# LED-zero-SHIM.net
KiCad netlist of a schematic drawn in EAGLE
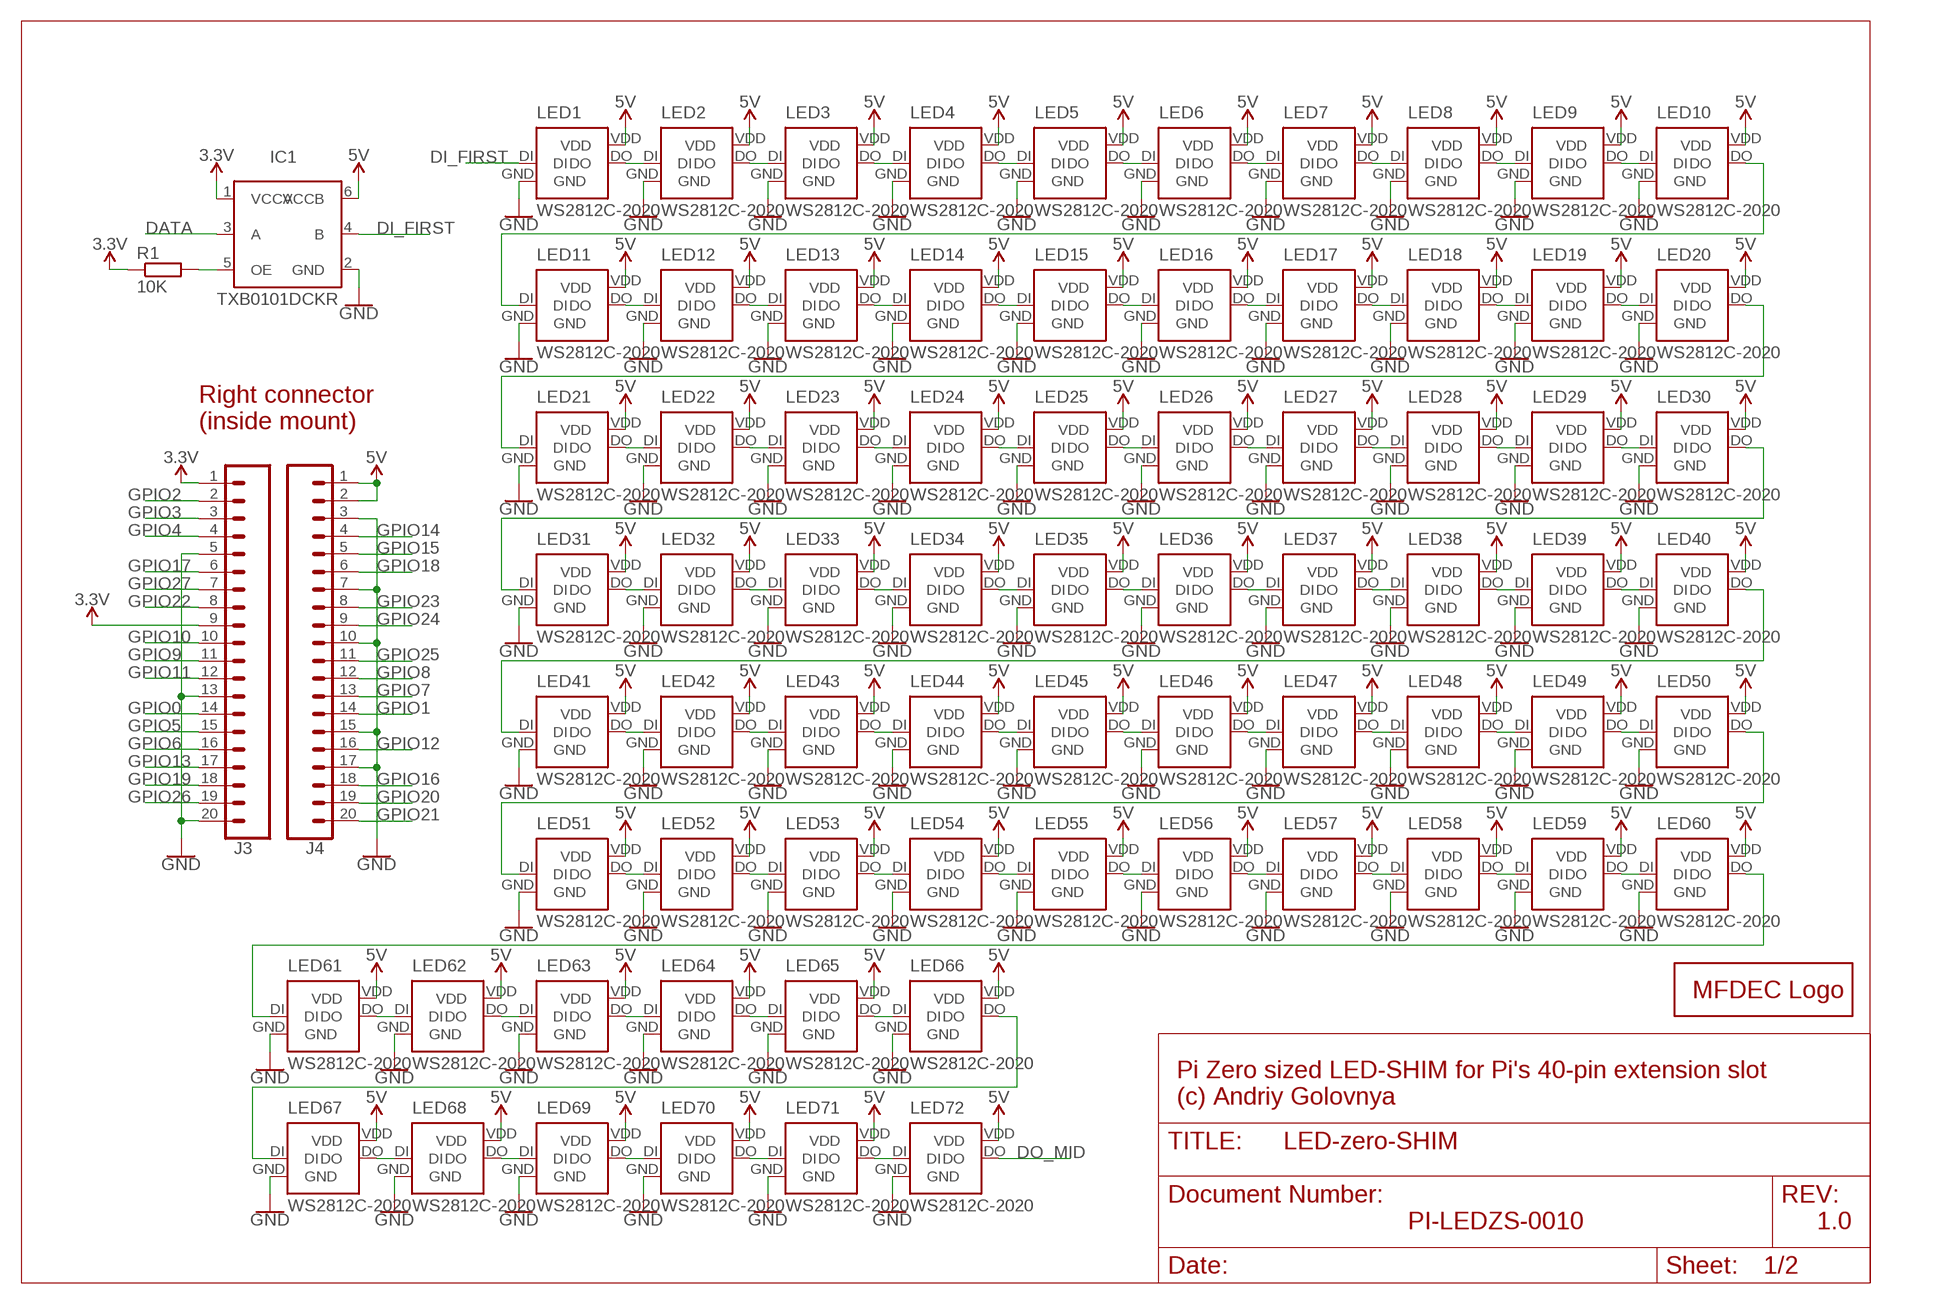
[diagram p0: schematic, sheet 1]
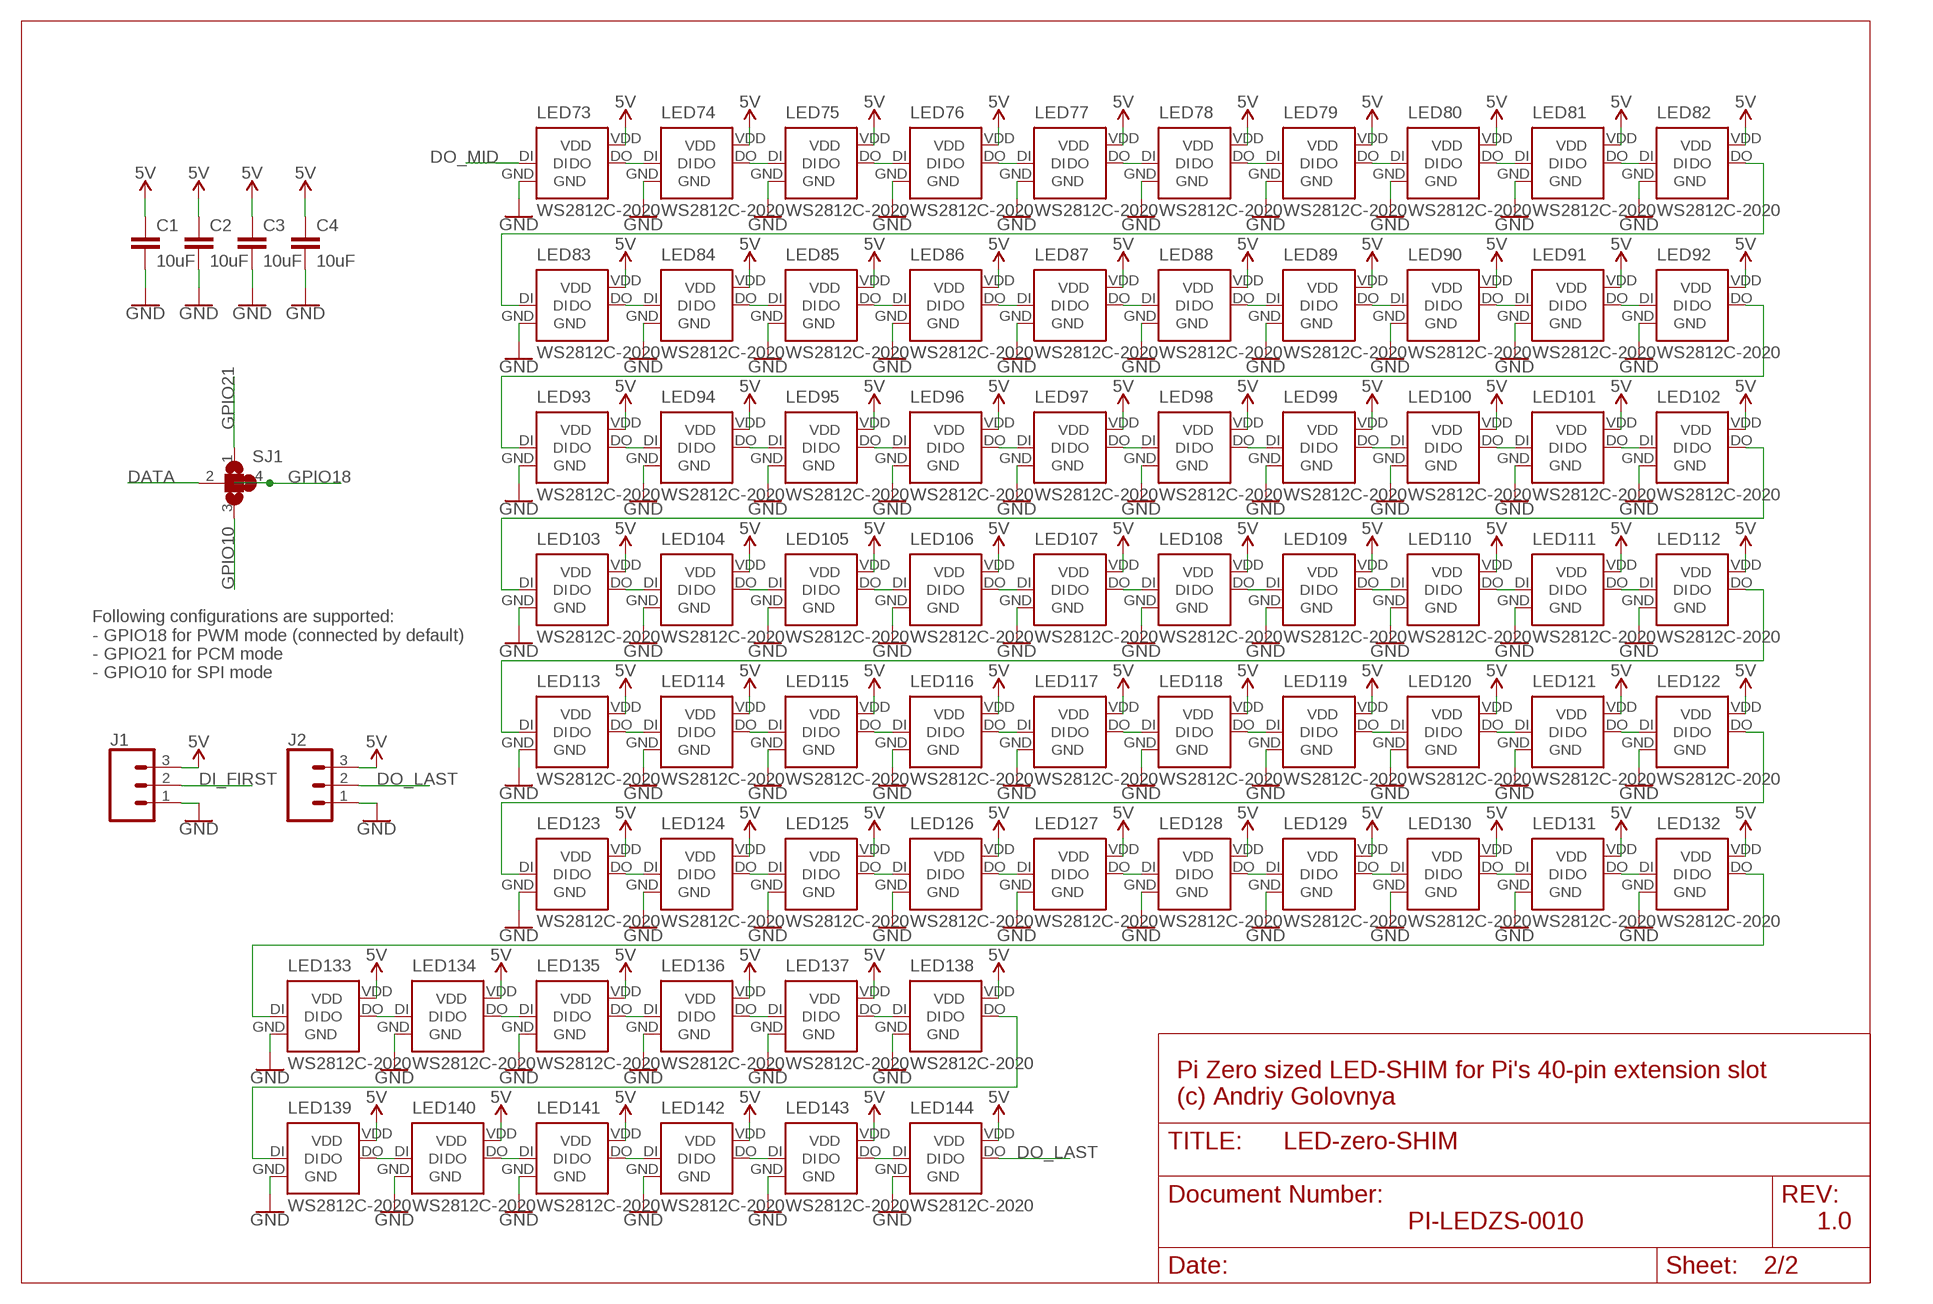
[diagram p1: schematic, sheet 2]

(export (version "E")
  (design (tool "Eeschema 10.0.6"))
  (components
    (comp (ref "IC1")
      (value "TXB0101DCKR")
      (footprint "eagle-import:SOT65P210X110-6N")
      (libsource (lib "eagle-import") (part "TXB0101DCKR"))
    )
    (comp (ref "J3")
      (value "CONN_20LOCK")
      (footprint "eagle-import:1X20_LOCK")
      (libsource (lib "eagle-import") (part "CONN_20LOCK"))
    )
    (comp (ref "J4")
      (value "CONN_20LOCK")
      (footprint "eagle-import:1X20_LOCK")
      (libsource (lib "eagle-import") (part "CONN_20LOCK"))
    )
    (comp (ref "LED1")
      (value "WS2812C-2020")
      (footprint "eagle-import:WS2812X-2020")
      (libsource (lib "eagle-import") (part "WS2812C-2020"))
    )
    (comp (ref "LED2")
      (value "WS2812C-2020")
      (footprint "eagle-import:WS2812X-2020")
      (libsource (lib "eagle-import") (part "WS2812C-2020"))
    )
    (comp (ref "LED3")
      (value "WS2812C-2020")
      (footprint "eagle-import:WS2812X-2020")
      (libsource (lib "eagle-import") (part "WS2812C-2020"))
    )
    (comp (ref "LED4")
      (value "WS2812C-2020")
      (footprint "eagle-import:WS2812X-2020")
      (libsource (lib "eagle-import") (part "WS2812C-2020"))
    )
    (comp (ref "LED5")
      (value "WS2812C-2020")
      (footprint "eagle-import:WS2812X-2020")
      (libsource (lib "eagle-import") (part "WS2812C-2020"))
    )
    (comp (ref "LED6")
      (value "WS2812C-2020")
      (footprint "eagle-import:WS2812X-2020")
      (libsource (lib "eagle-import") (part "WS2812C-2020"))
    )
    (comp (ref "LED7")
      (value "WS2812C-2020")
      (footprint "eagle-import:WS2812X-2020")
      (libsource (lib "eagle-import") (part "WS2812C-2020"))
    )
    (comp (ref "LED8")
      (value "WS2812C-2020")
      (footprint "eagle-import:WS2812X-2020")
      (libsource (lib "eagle-import") (part "WS2812C-2020"))
    )
    (comp (ref "LED9")
      (value "WS2812C-2020")
      (footprint "eagle-import:WS2812X-2020")
      (libsource (lib "eagle-import") (part "WS2812C-2020"))
    )
    (comp (ref "LED10")
      (value "WS2812C-2020")
      (footprint "eagle-import:WS2812X-2020")
      (libsource (lib "eagle-import") (part "WS2812C-2020"))
    )
    (comp (ref "LED11")
      (value "WS2812C-2020")
      (footprint "eagle-import:WS2812X-2020")
      (libsource (lib "eagle-import") (part "WS2812C-2020"))
    )
    (comp (ref "LED12")
      (value "WS2812C-2020")
      (footprint "eagle-import:WS2812X-2020")
      (libsource (lib "eagle-import") (part "WS2812C-2020"))
    )
    (comp (ref "LED13")
      (value "WS2812C-2020")
      (footprint "eagle-import:WS2812X-2020")
      (libsource (lib "eagle-import") (part "WS2812C-2020"))
    )
    (comp (ref "LED14")
      (value "WS2812C-2020")
      (footprint "eagle-import:WS2812X-2020")
      (libsource (lib "eagle-import") (part "WS2812C-2020"))
    )
    (comp (ref "LED15")
      (value "WS2812C-2020")
      (footprint "eagle-import:WS2812X-2020")
      (libsource (lib "eagle-import") (part "WS2812C-2020"))
    )
    (comp (ref "LED16")
      (value "WS2812C-2020")
      (footprint "eagle-import:WS2812X-2020")
      (libsource (lib "eagle-import") (part "WS2812C-2020"))
    )
    (comp (ref "LED17")
      (value "WS2812C-2020")
      (footprint "eagle-import:WS2812X-2020")
      (libsource (lib "eagle-import") (part "WS2812C-2020"))
    )
    (comp (ref "LED18")
      (value "WS2812C-2020")
      (footprint "eagle-import:WS2812X-2020")
      (libsource (lib "eagle-import") (part "WS2812C-2020"))
    )
    (comp (ref "LED19")
      (value "WS2812C-2020")
      (footprint "eagle-import:WS2812X-2020")
      (libsource (lib "eagle-import") (part "WS2812C-2020"))
    )
    (comp (ref "LED20")
      (value "WS2812C-2020")
      (footprint "eagle-import:WS2812X-2020")
      (libsource (lib "eagle-import") (part "WS2812C-2020"))
    )
    (comp (ref "LED21")
      (value "WS2812C-2020")
      (footprint "eagle-import:WS2812X-2020")
      (libsource (lib "eagle-import") (part "WS2812C-2020"))
    )
    (comp (ref "LED22")
      (value "WS2812C-2020")
      (footprint "eagle-import:WS2812X-2020")
      (libsource (lib "eagle-import") (part "WS2812C-2020"))
    )
    (comp (ref "LED23")
      (value "WS2812C-2020")
      (footprint "eagle-import:WS2812X-2020")
      (libsource (lib "eagle-import") (part "WS2812C-2020"))
    )
    (comp (ref "LED24")
      (value "WS2812C-2020")
      (footprint "eagle-import:WS2812X-2020")
      (libsource (lib "eagle-import") (part "WS2812C-2020"))
    )
    (comp (ref "LED25")
      (value "WS2812C-2020")
      (footprint "eagle-import:WS2812X-2020")
      (libsource (lib "eagle-import") (part "WS2812C-2020"))
    )
    (comp (ref "LED26")
      (value "WS2812C-2020")
      (footprint "eagle-import:WS2812X-2020")
      (libsource (lib "eagle-import") (part "WS2812C-2020"))
    )
    (comp (ref "LED27")
      (value "WS2812C-2020")
      (footprint "eagle-import:WS2812X-2020")
      (libsource (lib "eagle-import") (part "WS2812C-2020"))
    )
    (comp (ref "LED28")
      (value "WS2812C-2020")
      (footprint "eagle-import:WS2812X-2020")
      (libsource (lib "eagle-import") (part "WS2812C-2020"))
    )
    (comp (ref "LED29")
      (value "WS2812C-2020")
      (footprint "eagle-import:WS2812X-2020")
      (libsource (lib "eagle-import") (part "WS2812C-2020"))
    )
    (comp (ref "LED30")
      (value "WS2812C-2020")
      (footprint "eagle-import:WS2812X-2020")
      (libsource (lib "eagle-import") (part "WS2812C-2020"))
    )
    (comp (ref "LED31")
      (value "WS2812C-2020")
      (footprint "eagle-import:WS2812X-2020")
      (libsource (lib "eagle-import") (part "WS2812C-2020"))
    )
    (comp (ref "LED32")
      (value "WS2812C-2020")
      (footprint "eagle-import:WS2812X-2020")
      (libsource (lib "eagle-import") (part "WS2812C-2020"))
    )
    (comp (ref "LED33")
      (value "WS2812C-2020")
      (footprint "eagle-import:WS2812X-2020")
      (libsource (lib "eagle-import") (part "WS2812C-2020"))
    )
    (comp (ref "LED34")
      (value "WS2812C-2020")
      (footprint "eagle-import:WS2812X-2020")
      (libsource (lib "eagle-import") (part "WS2812C-2020"))
    )
    (comp (ref "LED35")
      (value "WS2812C-2020")
      (footprint "eagle-import:WS2812X-2020")
      (libsource (lib "eagle-import") (part "WS2812C-2020"))
    )
    (comp (ref "LED36")
      (value "WS2812C-2020")
      (footprint "eagle-import:WS2812X-2020")
      (libsource (lib "eagle-import") (part "WS2812C-2020"))
    )
    (comp (ref "LED37")
      (value "WS2812C-2020")
      (footprint "eagle-import:WS2812X-2020")
      (libsource (lib "eagle-import") (part "WS2812C-2020"))
    )
    (comp (ref "LED38")
      (value "WS2812C-2020")
      (footprint "eagle-import:WS2812X-2020")
      (libsource (lib "eagle-import") (part "WS2812C-2020"))
    )
    (comp (ref "LED39")
      (value "WS2812C-2020")
      (footprint "eagle-import:WS2812X-2020")
      (libsource (lib "eagle-import") (part "WS2812C-2020"))
    )
    (comp (ref "LED40")
      (value "WS2812C-2020")
      (footprint "eagle-import:WS2812X-2020")
      (libsource (lib "eagle-import") (part "WS2812C-2020"))
    )
    (comp (ref "LED41")
      (value "WS2812C-2020")
      (footprint "eagle-import:WS2812X-2020")
      (libsource (lib "eagle-import") (part "WS2812C-2020"))
    )
    (comp (ref "LED42")
      (value "WS2812C-2020")
      (footprint "eagle-import:WS2812X-2020")
      (libsource (lib "eagle-import") (part "WS2812C-2020"))
    )
    (comp (ref "LED43")
      (value "WS2812C-2020")
      (footprint "eagle-import:WS2812X-2020")
      (libsource (lib "eagle-import") (part "WS2812C-2020"))
    )
    (comp (ref "LED44")
      (value "WS2812C-2020")
      (footprint "eagle-import:WS2812X-2020")
      (libsource (lib "eagle-import") (part "WS2812C-2020"))
    )
    (comp (ref "LED45")
      (value "WS2812C-2020")
      (footprint "eagle-import:WS2812X-2020")
      (libsource (lib "eagle-import") (part "WS2812C-2020"))
    )
    (comp (ref "LED46")
      (value "WS2812C-2020")
      (footprint "eagle-import:WS2812X-2020")
      (libsource (lib "eagle-import") (part "WS2812C-2020"))
    )
    (comp (ref "LED47")
      (value "WS2812C-2020")
      (footprint "eagle-import:WS2812X-2020")
      (libsource (lib "eagle-import") (part "WS2812C-2020"))
    )
    (comp (ref "LED48")
      (value "WS2812C-2020")
      (footprint "eagle-import:WS2812X-2020")
      (libsource (lib "eagle-import") (part "WS2812C-2020"))
    )
    (comp (ref "LED49")
      (value "WS2812C-2020")
      (footprint "eagle-import:WS2812X-2020")
      (libsource (lib "eagle-import") (part "WS2812C-2020"))
    )
    (comp (ref "LED50")
      (value "WS2812C-2020")
      (footprint "eagle-import:WS2812X-2020")
      (libsource (lib "eagle-import") (part "WS2812C-2020"))
    )
    (comp (ref "LED51")
      (value "WS2812C-2020")
      (footprint "eagle-import:WS2812X-2020")
      (libsource (lib "eagle-import") (part "WS2812C-2020"))
    )
    (comp (ref "LED52")
      (value "WS2812C-2020")
      (footprint "eagle-import:WS2812X-2020")
      (libsource (lib "eagle-import") (part "WS2812C-2020"))
    )
    (comp (ref "LED53")
      (value "WS2812C-2020")
      (footprint "eagle-import:WS2812X-2020")
      (libsource (lib "eagle-import") (part "WS2812C-2020"))
    )
    (comp (ref "LED54")
      (value "WS2812C-2020")
      (footprint "eagle-import:WS2812X-2020")
      (libsource (lib "eagle-import") (part "WS2812C-2020"))
    )
    (comp (ref "LED55")
      (value "WS2812C-2020")
      (footprint "eagle-import:WS2812X-2020")
      (libsource (lib "eagle-import") (part "WS2812C-2020"))
    )
    (comp (ref "LED56")
      (value "WS2812C-2020")
      (footprint "eagle-import:WS2812X-2020")
      (libsource (lib "eagle-import") (part "WS2812C-2020"))
    )
    (comp (ref "LED57")
      (value "WS2812C-2020")
      (footprint "eagle-import:WS2812X-2020")
      (libsource (lib "eagle-import") (part "WS2812C-2020"))
    )
    (comp (ref "LED58")
      (value "WS2812C-2020")
      (footprint "eagle-import:WS2812X-2020")
      (libsource (lib "eagle-import") (part "WS2812C-2020"))
    )
    (comp (ref "LED59")
      (value "WS2812C-2020")
      (footprint "eagle-import:WS2812X-2020")
      (libsource (lib "eagle-import") (part "WS2812C-2020"))
    )
    (comp (ref "LED60")
      (value "WS2812C-2020")
      (footprint "eagle-import:WS2812X-2020")
      (libsource (lib "eagle-import") (part "WS2812C-2020"))
    )
    (comp (ref "LED61")
      (value "WS2812C-2020")
      (footprint "eagle-import:WS2812X-2020")
      (libsource (lib "eagle-import") (part "WS2812C-2020"))
    )
    (comp (ref "LED62")
      (value "WS2812C-2020")
      (footprint "eagle-import:WS2812X-2020")
      (libsource (lib "eagle-import") (part "WS2812C-2020"))
    )
    (comp (ref "LED63")
      (value "WS2812C-2020")
      (footprint "eagle-import:WS2812X-2020")
      (libsource (lib "eagle-import") (part "WS2812C-2020"))
    )
    (comp (ref "LED64")
      (value "WS2812C-2020")
      (footprint "eagle-import:WS2812X-2020")
      (libsource (lib "eagle-import") (part "WS2812C-2020"))
    )
    (comp (ref "LED65")
      (value "WS2812C-2020")
      (footprint "eagle-import:WS2812X-2020")
      (libsource (lib "eagle-import") (part "WS2812C-2020"))
    )
    (comp (ref "LED66")
      (value "WS2812C-2020")
      (footprint "eagle-import:WS2812X-2020")
      (libsource (lib "eagle-import") (part "WS2812C-2020"))
    )
    (comp (ref "LED67")
      (value "WS2812C-2020")
      (footprint "eagle-import:WS2812X-2020")
      (libsource (lib "eagle-import") (part "WS2812C-2020"))
    )
    (comp (ref "LED68")
      (value "WS2812C-2020")
      (footprint "eagle-import:WS2812X-2020")
      (libsource (lib "eagle-import") (part "WS2812C-2020"))
    )
    (comp (ref "LED69")
      (value "WS2812C-2020")
      (footprint "eagle-import:WS2812X-2020")
      (libsource (lib "eagle-import") (part "WS2812C-2020"))
    )
    (comp (ref "LED70")
      (value "WS2812C-2020")
      (footprint "eagle-import:WS2812X-2020")
      (libsource (lib "eagle-import") (part "WS2812C-2020"))
    )
    (comp (ref "LED71")
      (value "WS2812C-2020")
      (footprint "eagle-import:WS2812X-2020")
      (libsource (lib "eagle-import") (part "WS2812C-2020"))
    )
    (comp (ref "LED72")
      (value "WS2812C-2020")
      (footprint "eagle-import:WS2812X-2020")
      (libsource (lib "eagle-import") (part "WS2812C-2020"))
    )
    (comp (ref "LOGO1")
      (value "MFDECLOGO_L_30MM")
      (footprint "eagle-import:MFDEC_L_30MM")
      (libsource (lib "eagle-import") (part "MFDECLOGO_L_30MM"))
    )
    (comp (ref "R1")
      (value "10K")
      (footprint "eagle-import:R0402")
      (libsource (lib "eagle-import") (part "R-EU_R0402"))
    )
    (comp (ref "C1")
      (value "10uF")
      (footprint "eagle-import:C0805")
      (libsource (lib "eagle-import") (part "C-EUC0805"))
    )
    (comp (ref "C2")
      (value "10uF")
      (footprint "eagle-import:C0805")
      (libsource (lib "eagle-import") (part "C-EUC0805"))
    )
    (comp (ref "C3")
      (value "10uF")
      (footprint "eagle-import:C0805")
      (libsource (lib "eagle-import") (part "C-EUC0805"))
    )
    (comp (ref "C4")
      (value "10uF")
      (footprint "eagle-import:C0805")
      (libsource (lib "eagle-import") (part "C-EUC0805"))
    )
    (comp (ref "J1")
      (value "CONN_03")
      (footprint "eagle-import:1X03")
      (libsource (lib "eagle-import") (part "CONN_03"))
    )
    (comp (ref "J2")
      (value "CONN_03")
      (footprint "eagle-import:1X03")
      (libsource (lib "eagle-import") (part "CONN_03"))
    )
    (comp (ref "LED73")
      (value "WS2812C-2020")
      (footprint "eagle-import:WS2812X-2020")
      (libsource (lib "eagle-import") (part "WS2812C-2020"))
    )
    (comp (ref "LED74")
      (value "WS2812C-2020")
      (footprint "eagle-import:WS2812X-2020")
      (libsource (lib "eagle-import") (part "WS2812C-2020"))
    )
    (comp (ref "LED75")
      (value "WS2812C-2020")
      (footprint "eagle-import:WS2812X-2020")
      (libsource (lib "eagle-import") (part "WS2812C-2020"))
    )
    (comp (ref "LED76")
      (value "WS2812C-2020")
      (footprint "eagle-import:WS2812X-2020")
      (libsource (lib "eagle-import") (part "WS2812C-2020"))
    )
    (comp (ref "LED77")
      (value "WS2812C-2020")
      (footprint "eagle-import:WS2812X-2020")
      (libsource (lib "eagle-import") (part "WS2812C-2020"))
    )
    (comp (ref "LED78")
      (value "WS2812C-2020")
      (footprint "eagle-import:WS2812X-2020")
      (libsource (lib "eagle-import") (part "WS2812C-2020"))
    )
    (comp (ref "LED79")
      (value "WS2812C-2020")
      (footprint "eagle-import:WS2812X-2020")
      (libsource (lib "eagle-import") (part "WS2812C-2020"))
    )
    (comp (ref "LED80")
      (value "WS2812C-2020")
      (footprint "eagle-import:WS2812X-2020")
      (libsource (lib "eagle-import") (part "WS2812C-2020"))
    )
    (comp (ref "LED81")
      (value "WS2812C-2020")
      (footprint "eagle-import:WS2812X-2020")
      (libsource (lib "eagle-import") (part "WS2812C-2020"))
    )
    (comp (ref "LED82")
      (value "WS2812C-2020")
      (footprint "eagle-import:WS2812X-2020")
      (libsource (lib "eagle-import") (part "WS2812C-2020"))
    )
    (comp (ref "LED83")
      (value "WS2812C-2020")
      (footprint "eagle-import:WS2812X-2020")
      (libsource (lib "eagle-import") (part "WS2812C-2020"))
    )
    (comp (ref "LED84")
      (value "WS2812C-2020")
      (footprint "eagle-import:WS2812X-2020")
      (libsource (lib "eagle-import") (part "WS2812C-2020"))
    )
    (comp (ref "LED85")
      (value "WS2812C-2020")
      (footprint "eagle-import:WS2812X-2020")
      (libsource (lib "eagle-import") (part "WS2812C-2020"))
    )
    (comp (ref "LED86")
      (value "WS2812C-2020")
      (footprint "eagle-import:WS2812X-2020")
      (libsource (lib "eagle-import") (part "WS2812C-2020"))
    )
    (comp (ref "LED87")
      (value "WS2812C-2020")
      (footprint "eagle-import:WS2812X-2020")
      (libsource (lib "eagle-import") (part "WS2812C-2020"))
    )
    (comp (ref "LED88")
      (value "WS2812C-2020")
      (footprint "eagle-import:WS2812X-2020")
      (libsource (lib "eagle-import") (part "WS2812C-2020"))
    )
    (comp (ref "LED89")
      (value "WS2812C-2020")
      (footprint "eagle-import:WS2812X-2020")
      (libsource (lib "eagle-import") (part "WS2812C-2020"))
    )
    (comp (ref "LED90")
      (value "WS2812C-2020")
      (footprint "eagle-import:WS2812X-2020")
      (libsource (lib "eagle-import") (part "WS2812C-2020"))
    )
    (comp (ref "LED91")
      (value "WS2812C-2020")
      (footprint "eagle-import:WS2812X-2020")
      (libsource (lib "eagle-import") (part "WS2812C-2020"))
    )
    (comp (ref "LED92")
      (value "WS2812C-2020")
      (footprint "eagle-import:WS2812X-2020")
      (libsource (lib "eagle-import") (part "WS2812C-2020"))
    )
    (comp (ref "LED93")
      (value "WS2812C-2020")
      (footprint "eagle-import:WS2812X-2020")
      (libsource (lib "eagle-import") (part "WS2812C-2020"))
    )
    (comp (ref "LED94")
      (value "WS2812C-2020")
      (footprint "eagle-import:WS2812X-2020")
      (libsource (lib "eagle-import") (part "WS2812C-2020"))
    )
    (comp (ref "LED95")
      (value "WS2812C-2020")
      (footprint "eagle-import:WS2812X-2020")
      (libsource (lib "eagle-import") (part "WS2812C-2020"))
    )
    (comp (ref "LED96")
      (value "WS2812C-2020")
      (footprint "eagle-import:WS2812X-2020")
      (libsource (lib "eagle-import") (part "WS2812C-2020"))
    )
    (comp (ref "LED97")
      (value "WS2812C-2020")
      (footprint "eagle-import:WS2812X-2020")
      (libsource (lib "eagle-import") (part "WS2812C-2020"))
    )
    (comp (ref "LED98")
      (value "WS2812C-2020")
      (footprint "eagle-import:WS2812X-2020")
      (libsource (lib "eagle-import") (part "WS2812C-2020"))
    )
    (comp (ref "LED99")
      (value "WS2812C-2020")
      (footprint "eagle-import:WS2812X-2020")
      (libsource (lib "eagle-import") (part "WS2812C-2020"))
    )
    (comp (ref "LED100")
      (value "WS2812C-2020")
      (footprint "eagle-import:WS2812X-2020")
      (libsource (lib "eagle-import") (part "WS2812C-2020"))
    )
    (comp (ref "LED101")
      (value "WS2812C-2020")
      (footprint "eagle-import:WS2812X-2020")
      (libsource (lib "eagle-import") (part "WS2812C-2020"))
    )
    (comp (ref "LED102")
      (value "WS2812C-2020")
      (footprint "eagle-import:WS2812X-2020")
      (libsource (lib "eagle-import") (part "WS2812C-2020"))
    )
    (comp (ref "LED103")
      (value "WS2812C-2020")
      (footprint "eagle-import:WS2812X-2020")
      (libsource (lib "eagle-import") (part "WS2812C-2020"))
    )
    (comp (ref "LED104")
      (value "WS2812C-2020")
      (footprint "eagle-import:WS2812X-2020")
      (libsource (lib "eagle-import") (part "WS2812C-2020"))
    )
    (comp (ref "LED105")
      (value "WS2812C-2020")
      (footprint "eagle-import:WS2812X-2020")
      (libsource (lib "eagle-import") (part "WS2812C-2020"))
    )
    (comp (ref "LED106")
      (value "WS2812C-2020")
      (footprint "eagle-import:WS2812X-2020")
      (libsource (lib "eagle-import") (part "WS2812C-2020"))
    )
    (comp (ref "LED107")
      (value "WS2812C-2020")
      (footprint "eagle-import:WS2812X-2020")
      (libsource (lib "eagle-import") (part "WS2812C-2020"))
    )
    (comp (ref "LED108")
      (value "WS2812C-2020")
      (footprint "eagle-import:WS2812X-2020")
      (libsource (lib "eagle-import") (part "WS2812C-2020"))
    )
    (comp (ref "LED109")
      (value "WS2812C-2020")
      (footprint "eagle-import:WS2812X-2020")
      (libsource (lib "eagle-import") (part "WS2812C-2020"))
    )
    (comp (ref "LED110")
      (value "WS2812C-2020")
      (footprint "eagle-import:WS2812X-2020")
      (libsource (lib "eagle-import") (part "WS2812C-2020"))
    )
    (comp (ref "LED111")
      (value "WS2812C-2020")
      (footprint "eagle-import:WS2812X-2020")
      (libsource (lib "eagle-import") (part "WS2812C-2020"))
    )
    (comp (ref "LED112")
      (value "WS2812C-2020")
      (footprint "eagle-import:WS2812X-2020")
      (libsource (lib "eagle-import") (part "WS2812C-2020"))
    )
    (comp (ref "LED113")
      (value "WS2812C-2020")
      (footprint "eagle-import:WS2812X-2020")
      (libsource (lib "eagle-import") (part "WS2812C-2020"))
    )
    (comp (ref "LED114")
      (value "WS2812C-2020")
      (footprint "eagle-import:WS2812X-2020")
      (libsource (lib "eagle-import") (part "WS2812C-2020"))
    )
    (comp (ref "LED115")
      (value "WS2812C-2020")
      (footprint "eagle-import:WS2812X-2020")
      (libsource (lib "eagle-import") (part "WS2812C-2020"))
    )
    (comp (ref "LED116")
      (value "WS2812C-2020")
      (footprint "eagle-import:WS2812X-2020")
      (libsource (lib "eagle-import") (part "WS2812C-2020"))
    )
    (comp (ref "LED117")
      (value "WS2812C-2020")
      (footprint "eagle-import:WS2812X-2020")
      (libsource (lib "eagle-import") (part "WS2812C-2020"))
    )
    (comp (ref "LED118")
      (value "WS2812C-2020")
      (footprint "eagle-import:WS2812X-2020")
      (libsource (lib "eagle-import") (part "WS2812C-2020"))
    )
    (comp (ref "LED119")
      (value "WS2812C-2020")
      (footprint "eagle-import:WS2812X-2020")
      (libsource (lib "eagle-import") (part "WS2812C-2020"))
    )
    (comp (ref "LED120")
      (value "WS2812C-2020")
      (footprint "eagle-import:WS2812X-2020")
      (libsource (lib "eagle-import") (part "WS2812C-2020"))
    )
    (comp (ref "LED121")
      (value "WS2812C-2020")
      (footprint "eagle-import:WS2812X-2020")
      (libsource (lib "eagle-import") (part "WS2812C-2020"))
    )
    (comp (ref "LED122")
      (value "WS2812C-2020")
      (footprint "eagle-import:WS2812X-2020")
      (libsource (lib "eagle-import") (part "WS2812C-2020"))
    )
    (comp (ref "LED123")
      (value "WS2812C-2020")
      (footprint "eagle-import:WS2812X-2020")
      (libsource (lib "eagle-import") (part "WS2812C-2020"))
    )
    (comp (ref "LED124")
      (value "WS2812C-2020")
      (footprint "eagle-import:WS2812X-2020")
      (libsource (lib "eagle-import") (part "WS2812C-2020"))
    )
    (comp (ref "LED125")
      (value "WS2812C-2020")
      (footprint "eagle-import:WS2812X-2020")
      (libsource (lib "eagle-import") (part "WS2812C-2020"))
    )
    (comp (ref "LED126")
      (value "WS2812C-2020")
      (footprint "eagle-import:WS2812X-2020")
      (libsource (lib "eagle-import") (part "WS2812C-2020"))
    )
    (comp (ref "LED127")
      (value "WS2812C-2020")
      (footprint "eagle-import:WS2812X-2020")
      (libsource (lib "eagle-import") (part "WS2812C-2020"))
    )
    (comp (ref "LED128")
      (value "WS2812C-2020")
      (footprint "eagle-import:WS2812X-2020")
      (libsource (lib "eagle-import") (part "WS2812C-2020"))
    )
    (comp (ref "LED129")
      (value "WS2812C-2020")
      (footprint "eagle-import:WS2812X-2020")
      (libsource (lib "eagle-import") (part "WS2812C-2020"))
    )
    (comp (ref "LED130")
      (value "WS2812C-2020")
      (footprint "eagle-import:WS2812X-2020")
      (libsource (lib "eagle-import") (part "WS2812C-2020"))
    )
    (comp (ref "LED131")
      (value "WS2812C-2020")
      (footprint "eagle-import:WS2812X-2020")
      (libsource (lib "eagle-import") (part "WS2812C-2020"))
    )
    (comp (ref "LED132")
      (value "WS2812C-2020")
      (footprint "eagle-import:WS2812X-2020")
      (libsource (lib "eagle-import") (part "WS2812C-2020"))
    )
    (comp (ref "LED133")
      (value "WS2812C-2020")
      (footprint "eagle-import:WS2812X-2020")
      (libsource (lib "eagle-import") (part "WS2812C-2020"))
    )
    (comp (ref "LED134")
      (value "WS2812C-2020")
      (footprint "eagle-import:WS2812X-2020")
      (libsource (lib "eagle-import") (part "WS2812C-2020"))
    )
    (comp (ref "LED135")
      (value "WS2812C-2020")
      (footprint "eagle-import:WS2812X-2020")
      (libsource (lib "eagle-import") (part "WS2812C-2020"))
    )
    (comp (ref "LED136")
      (value "WS2812C-2020")
      (footprint "eagle-import:WS2812X-2020")
      (libsource (lib "eagle-import") (part "WS2812C-2020"))
    )
    (comp (ref "LED137")
      (value "WS2812C-2020")
      (footprint "eagle-import:WS2812X-2020")
      (libsource (lib "eagle-import") (part "WS2812C-2020"))
    )
    (comp (ref "LED138")
      (value "WS2812C-2020")
      (footprint "eagle-import:WS2812X-2020")
      (libsource (lib "eagle-import") (part "WS2812C-2020"))
    )
    (comp (ref "LED139")
      (value "WS2812C-2020")
      (footprint "eagle-import:WS2812X-2020")
      (libsource (lib "eagle-import") (part "WS2812C-2020"))
    )
    (comp (ref "LED140")
      (value "WS2812C-2020")
      (footprint "eagle-import:WS2812X-2020")
      (libsource (lib "eagle-import") (part "WS2812C-2020"))
    )
    (comp (ref "LED141")
      (value "WS2812C-2020")
      (footprint "eagle-import:WS2812X-2020")
      (libsource (lib "eagle-import") (part "WS2812C-2020"))
    )
    (comp (ref "LED142")
      (value "WS2812C-2020")
      (footprint "eagle-import:WS2812X-2020")
      (libsource (lib "eagle-import") (part "WS2812C-2020"))
    )
    (comp (ref "LED143")
      (value "WS2812C-2020")
      (footprint "eagle-import:WS2812X-2020")
      (libsource (lib "eagle-import") (part "WS2812C-2020"))
    )
    (comp (ref "LED144")
      (value "WS2812C-2020")
      (footprint "eagle-import:WS2812X-2020")
      (libsource (lib "eagle-import") (part "WS2812C-2020"))
    )
    (comp (ref "SJ1")
      (value "SJ3")
      (footprint "eagle-import:SJ_3")
      (libsource (lib "eagle-import") (part "SJ3"))
    )
  )
  (nets
    (net (code "1") (name "3.3V") (class "Default")
      (node (ref "IC1") (pin "1") (pinfunction "VCCA_1") (pintype "power_in"))
      (node (ref "J3") (pin "1") (pinfunction "1_1") (pintype "passive"))
      (node (ref "J3") (pin "9") (pinfunction "9_9") (pintype "passive"))
      (node (ref "R1") (pin "1") (pinfunction "1_1") (pintype "passive"))
    )
    (net (code "2") (name "5V") (class "Default")
      (node (ref "C1") (pin "1") (pinfunction "1_1") (pintype "passive"))
      (node (ref "C2") (pin "1") (pinfunction "1_1") (pintype "passive"))
      (node (ref "C3") (pin "1") (pinfunction "1_1") (pintype "passive"))
      (node (ref "C4") (pin "1") (pinfunction "1_1") (pintype "passive"))
      (node (ref "IC1") (pin "6") (pinfunction "VCCB_6") (pintype "power_in"))
      (node (ref "J1") (pin "3") (pinfunction "3_3") (pintype "passive"))
      (node (ref "J2") (pin "3") (pinfunction "3_3") (pintype "passive"))
      (node (ref "J4") (pin "1") (pinfunction "1_1") (pintype "passive"))
      (node (ref "J4") (pin "2") (pinfunction "2_2") (pintype "passive"))
      (node (ref "LED1") (pin "VDD") (pinfunction "VDD_VDD") (pintype "power_in"))
      (node (ref "LED10") (pin "VDD") (pinfunction "VDD_VDD") (pintype "power_in"))
      (node (ref "LED100") (pin "VDD") (pinfunction "VDD_VDD") (pintype "power_in"))
      (node (ref "LED101") (pin "VDD") (pinfunction "VDD_VDD") (pintype "power_in"))
      (node (ref "LED102") (pin "VDD") (pinfunction "VDD_VDD") (pintype "power_in"))
      (node (ref "LED103") (pin "VDD") (pinfunction "VDD_VDD") (pintype "power_in"))
      (node (ref "LED104") (pin "VDD") (pinfunction "VDD_VDD") (pintype "power_in"))
      (node (ref "LED105") (pin "VDD") (pinfunction "VDD_VDD") (pintype "power_in"))
      (node (ref "LED106") (pin "VDD") (pinfunction "VDD_VDD") (pintype "power_in"))
      (node (ref "LED107") (pin "VDD") (pinfunction "VDD_VDD") (pintype "power_in"))
      (node (ref "LED108") (pin "VDD") (pinfunction "VDD_VDD") (pintype "power_in"))
      (node (ref "LED109") (pin "VDD") (pinfunction "VDD_VDD") (pintype "power_in"))
      (node (ref "LED11") (pin "VDD") (pinfunction "VDD_VDD") (pintype "power_in"))
      (node (ref "LED110") (pin "VDD") (pinfunction "VDD_VDD") (pintype "power_in"))
      (node (ref "LED111") (pin "VDD") (pinfunction "VDD_VDD") (pintype "power_in"))
      (node (ref "LED112") (pin "VDD") (pinfunction "VDD_VDD") (pintype "power_in"))
      (node (ref "LED113") (pin "VDD") (pinfunction "VDD_VDD") (pintype "power_in"))
      (node (ref "LED114") (pin "VDD") (pinfunction "VDD_VDD") (pintype "power_in"))
      (node (ref "LED115") (pin "VDD") (pinfunction "VDD_VDD") (pintype "power_in"))
      (node (ref "LED116") (pin "VDD") (pinfunction "VDD_VDD") (pintype "power_in"))
      (node (ref "LED117") (pin "VDD") (pinfunction "VDD_VDD") (pintype "power_in"))
      (node (ref "LED118") (pin "VDD") (pinfunction "VDD_VDD") (pintype "power_in"))
      (node (ref "LED119") (pin "VDD") (pinfunction "VDD_VDD") (pintype "power_in"))
      (node (ref "LED12") (pin "VDD") (pinfunction "VDD_VDD") (pintype "power_in"))
      (node (ref "LED120") (pin "VDD") (pinfunction "VDD_VDD") (pintype "power_in"))
      (node (ref "LED121") (pin "VDD") (pinfunction "VDD_VDD") (pintype "power_in"))
      (node (ref "LED122") (pin "VDD") (pinfunction "VDD_VDD") (pintype "power_in"))
      (node (ref "LED123") (pin "VDD") (pinfunction "VDD_VDD") (pintype "power_in"))
      (node (ref "LED124") (pin "VDD") (pinfunction "VDD_VDD") (pintype "power_in"))
      (node (ref "LED125") (pin "VDD") (pinfunction "VDD_VDD") (pintype "power_in"))
      (node (ref "LED126") (pin "VDD") (pinfunction "VDD_VDD") (pintype "power_in"))
      (node (ref "LED127") (pin "VDD") (pinfunction "VDD_VDD") (pintype "power_in"))
      (node (ref "LED128") (pin "VDD") (pinfunction "VDD_VDD") (pintype "power_in"))
      (node (ref "LED129") (pin "VDD") (pinfunction "VDD_VDD") (pintype "power_in"))
      (node (ref "LED13") (pin "VDD") (pinfunction "VDD_VDD") (pintype "power_in"))
      (node (ref "LED130") (pin "VDD") (pinfunction "VDD_VDD") (pintype "power_in"))
      (node (ref "LED131") (pin "VDD") (pinfunction "VDD_VDD") (pintype "power_in"))
      (node (ref "LED132") (pin "VDD") (pinfunction "VDD_VDD") (pintype "power_in"))
      (node (ref "LED133") (pin "VDD") (pinfunction "VDD_VDD") (pintype "power_in"))
      (node (ref "LED134") (pin "VDD") (pinfunction "VDD_VDD") (pintype "power_in"))
      (node (ref "LED135") (pin "VDD") (pinfunction "VDD_VDD") (pintype "power_in"))
      (node (ref "LED136") (pin "VDD") (pinfunction "VDD_VDD") (pintype "power_in"))
      (node (ref "LED137") (pin "VDD") (pinfunction "VDD_VDD") (pintype "power_in"))
      (node (ref "LED138") (pin "VDD") (pinfunction "VDD_VDD") (pintype "power_in"))
      (node (ref "LED139") (pin "VDD") (pinfunction "VDD_VDD") (pintype "power_in"))
      (node (ref "LED14") (pin "VDD") (pinfunction "VDD_VDD") (pintype "power_in"))
      (node (ref "LED140") (pin "VDD") (pinfunction "VDD_VDD") (pintype "power_in"))
      (node (ref "LED141") (pin "VDD") (pinfunction "VDD_VDD") (pintype "power_in"))
      (node (ref "LED142") (pin "VDD") (pinfunction "VDD_VDD") (pintype "power_in"))
      (node (ref "LED143") (pin "VDD") (pinfunction "VDD_VDD") (pintype "power_in"))
      (node (ref "LED144") (pin "VDD") (pinfunction "VDD_VDD") (pintype "power_in"))
      (node (ref "LED15") (pin "VDD") (pinfunction "VDD_VDD") (pintype "power_in"))
      (node (ref "LED16") (pin "VDD") (pinfunction "VDD_VDD") (pintype "power_in"))
      (node (ref "LED17") (pin "VDD") (pinfunction "VDD_VDD") (pintype "power_in"))
      (node (ref "LED18") (pin "VDD") (pinfunction "VDD_VDD") (pintype "power_in"))
      (node (ref "LED19") (pin "VDD") (pinfunction "VDD_VDD") (pintype "power_in"))
      (node (ref "LED2") (pin "VDD") (pinfunction "VDD_VDD") (pintype "power_in"))
      (node (ref "LED20") (pin "VDD") (pinfunction "VDD_VDD") (pintype "power_in"))
      (node (ref "LED21") (pin "VDD") (pinfunction "VDD_VDD") (pintype "power_in"))
      (node (ref "LED22") (pin "VDD") (pinfunction "VDD_VDD") (pintype "power_in"))
      (node (ref "LED23") (pin "VDD") (pinfunction "VDD_VDD") (pintype "power_in"))
      (node (ref "LED24") (pin "VDD") (pinfunction "VDD_VDD") (pintype "power_in"))
      (node (ref "LED25") (pin "VDD") (pinfunction "VDD_VDD") (pintype "power_in"))
      (node (ref "LED26") (pin "VDD") (pinfunction "VDD_VDD") (pintype "power_in"))
      (node (ref "LED27") (pin "VDD") (pinfunction "VDD_VDD") (pintype "power_in"))
      (node (ref "LED28") (pin "VDD") (pinfunction "VDD_VDD") (pintype "power_in"))
      (node (ref "LED29") (pin "VDD") (pinfunction "VDD_VDD") (pintype "power_in"))
      (node (ref "LED3") (pin "VDD") (pinfunction "VDD_VDD") (pintype "power_in"))
      (node (ref "LED30") (pin "VDD") (pinfunction "VDD_VDD") (pintype "power_in"))
      (node (ref "LED31") (pin "VDD") (pinfunction "VDD_VDD") (pintype "power_in"))
      (node (ref "LED32") (pin "VDD") (pinfunction "VDD_VDD") (pintype "power_in"))
      (node (ref "LED33") (pin "VDD") (pinfunction "VDD_VDD") (pintype "power_in"))
      (node (ref "LED34") (pin "VDD") (pinfunction "VDD_VDD") (pintype "power_in"))
      (node (ref "LED35") (pin "VDD") (pinfunction "VDD_VDD") (pintype "power_in"))
      (node (ref "LED36") (pin "VDD") (pinfunction "VDD_VDD") (pintype "power_in"))
      (node (ref "LED37") (pin "VDD") (pinfunction "VDD_VDD") (pintype "power_in"))
      (node (ref "LED38") (pin "VDD") (pinfunction "VDD_VDD") (pintype "power_in"))
      (node (ref "LED39") (pin "VDD") (pinfunction "VDD_VDD") (pintype "power_in"))
      (node (ref "LED4") (pin "VDD") (pinfunction "VDD_VDD") (pintype "power_in"))
      (node (ref "LED40") (pin "VDD") (pinfunction "VDD_VDD") (pintype "power_in"))
      (node (ref "LED41") (pin "VDD") (pinfunction "VDD_VDD") (pintype "power_in"))
      (node (ref "LED42") (pin "VDD") (pinfunction "VDD_VDD") (pintype "power_in"))
      (node (ref "LED43") (pin "VDD") (pinfunction "VDD_VDD") (pintype "power_in"))
      (node (ref "LED44") (pin "VDD") (pinfunction "VDD_VDD") (pintype "power_in"))
      (node (ref "LED45") (pin "VDD") (pinfunction "VDD_VDD") (pintype "power_in"))
      (node (ref "LED46") (pin "VDD") (pinfunction "VDD_VDD") (pintype "power_in"))
      (node (ref "LED47") (pin "VDD") (pinfunction "VDD_VDD") (pintype "power_in"))
      (node (ref "LED48") (pin "VDD") (pinfunction "VDD_VDD") (pintype "power_in"))
      (node (ref "LED49") (pin "VDD") (pinfunction "VDD_VDD") (pintype "power_in"))
      (node (ref "LED5") (pin "VDD") (pinfunction "VDD_VDD") (pintype "power_in"))
      (node (ref "LED50") (pin "VDD") (pinfunction "VDD_VDD") (pintype "power_in"))
      (node (ref "LED51") (pin "VDD") (pinfunction "VDD_VDD") (pintype "power_in"))
      (node (ref "LED52") (pin "VDD") (pinfunction "VDD_VDD") (pintype "power_in"))
      (node (ref "LED53") (pin "VDD") (pinfunction "VDD_VDD") (pintype "power_in"))
      (node (ref "LED54") (pin "VDD") (pinfunction "VDD_VDD") (pintype "power_in"))
      (node (ref "LED55") (pin "VDD") (pinfunction "VDD_VDD") (pintype "power_in"))
      (node (ref "LED56") (pin "VDD") (pinfunction "VDD_VDD") (pintype "power_in"))
      (node (ref "LED57") (pin "VDD") (pinfunction "VDD_VDD") (pintype "power_in"))
      (node (ref "LED58") (pin "VDD") (pinfunction "VDD_VDD") (pintype "power_in"))
      (node (ref "LED59") (pin "VDD") (pinfunction "VDD_VDD") (pintype "power_in"))
      (node (ref "LED6") (pin "VDD") (pinfunction "VDD_VDD") (pintype "power_in"))
      (node (ref "LED60") (pin "VDD") (pinfunction "VDD_VDD") (pintype "power_in"))
      (node (ref "LED61") (pin "VDD") (pinfunction "VDD_VDD") (pintype "power_in"))
      (node (ref "LED62") (pin "VDD") (pinfunction "VDD_VDD") (pintype "power_in"))
      (node (ref "LED63") (pin "VDD") (pinfunction "VDD_VDD") (pintype "power_in"))
      (node (ref "LED64") (pin "VDD") (pinfunction "VDD_VDD") (pintype "power_in"))
      (node (ref "LED65") (pin "VDD") (pinfunction "VDD_VDD") (pintype "power_in"))
      (node (ref "LED66") (pin "VDD") (pinfunction "VDD_VDD") (pintype "power_in"))
      (node (ref "LED67") (pin "VDD") (pinfunction "VDD_VDD") (pintype "power_in"))
      (node (ref "LED68") (pin "VDD") (pinfunction "VDD_VDD") (pintype "power_in"))
      (node (ref "LED69") (pin "VDD") (pinfunction "VDD_VDD") (pintype "power_in"))
      (node (ref "LED7") (pin "VDD") (pinfunction "VDD_VDD") (pintype "power_in"))
      (node (ref "LED70") (pin "VDD") (pinfunction "VDD_VDD") (pintype "power_in"))
      (node (ref "LED71") (pin "VDD") (pinfunction "VDD_VDD") (pintype "power_in"))
      (node (ref "LED72") (pin "VDD") (pinfunction "VDD_VDD") (pintype "power_in"))
      (node (ref "LED73") (pin "VDD") (pinfunction "VDD_VDD") (pintype "power_in"))
      (node (ref "LED74") (pin "VDD") (pinfunction "VDD_VDD") (pintype "power_in"))
      (node (ref "LED75") (pin "VDD") (pinfunction "VDD_VDD") (pintype "power_in"))
      (node (ref "LED76") (pin "VDD") (pinfunction "VDD_VDD") (pintype "power_in"))
      (node (ref "LED77") (pin "VDD") (pinfunction "VDD_VDD") (pintype "power_in"))
      (node (ref "LED78") (pin "VDD") (pinfunction "VDD_VDD") (pintype "power_in"))
      (node (ref "LED79") (pin "VDD") (pinfunction "VDD_VDD") (pintype "power_in"))
      (node (ref "LED8") (pin "VDD") (pinfunction "VDD_VDD") (pintype "power_in"))
      (node (ref "LED80") (pin "VDD") (pinfunction "VDD_VDD") (pintype "power_in"))
      (node (ref "LED81") (pin "VDD") (pinfunction "VDD_VDD") (pintype "power_in"))
      (node (ref "LED82") (pin "VDD") (pinfunction "VDD_VDD") (pintype "power_in"))
      (node (ref "LED83") (pin "VDD") (pinfunction "VDD_VDD") (pintype "power_in"))
      (node (ref "LED84") (pin "VDD") (pinfunction "VDD_VDD") (pintype "power_in"))
      (node (ref "LED85") (pin "VDD") (pinfunction "VDD_VDD") (pintype "power_in"))
      (node (ref "LED86") (pin "VDD") (pinfunction "VDD_VDD") (pintype "power_in"))
      (node (ref "LED87") (pin "VDD") (pinfunction "VDD_VDD") (pintype "power_in"))
      (node (ref "LED88") (pin "VDD") (pinfunction "VDD_VDD") (pintype "power_in"))
      (node (ref "LED89") (pin "VDD") (pinfunction "VDD_VDD") (pintype "power_in"))
      (node (ref "LED9") (pin "VDD") (pinfunction "VDD_VDD") (pintype "power_in"))
      (node (ref "LED90") (pin "VDD") (pinfunction "VDD_VDD") (pintype "power_in"))
      (node (ref "LED91") (pin "VDD") (pinfunction "VDD_VDD") (pintype "power_in"))
      (node (ref "LED92") (pin "VDD") (pinfunction "VDD_VDD") (pintype "power_in"))
      (node (ref "LED93") (pin "VDD") (pinfunction "VDD_VDD") (pintype "power_in"))
      (node (ref "LED94") (pin "VDD") (pinfunction "VDD_VDD") (pintype "power_in"))
      (node (ref "LED95") (pin "VDD") (pinfunction "VDD_VDD") (pintype "power_in"))
      (node (ref "LED96") (pin "VDD") (pinfunction "VDD_VDD") (pintype "power_in"))
      (node (ref "LED97") (pin "VDD") (pinfunction "VDD_VDD") (pintype "power_in"))
      (node (ref "LED98") (pin "VDD") (pinfunction "VDD_VDD") (pintype "power_in"))
      (node (ref "LED99") (pin "VDD") (pinfunction "VDD_VDD") (pintype "power_in"))
    )
    (net (code "3") (name "DATA") (class "Default")
      (node (ref "IC1") (pin "3") (pinfunction "A_3") (pintype "bidirectional"))
      (node (ref "SJ1") (pin "2") (pinfunction "2_2") (pintype "passive"))
    )
    (net (code "4") (name "DI_FIRST") (class "Default")
      (node (ref "IC1") (pin "4") (pinfunction "B_4") (pintype "bidirectional"))
      (node (ref "J1") (pin "2") (pinfunction "2_2") (pintype "passive"))
      (node (ref "LED1") (pin "DI") (pinfunction "DI_DI") (pintype "input"))
    )
    (net (code "5") (name "DO_LAST") (class "Default")
      (node (ref "J2") (pin "2") (pinfunction "2_2") (pintype "passive"))
      (node (ref "LED144") (pin "DO") (pinfunction "DO_DO") (pintype "output"))
    )
    (net (code "6") (name "DO_MID") (class "Default")
      (node (ref "LED72") (pin "DO") (pinfunction "DO_DO") (pintype "output"))
      (node (ref "LED73") (pin "DI") (pinfunction "DI_DI") (pintype "input"))
    )
    (net (code "7") (name "GND") (class "Default")
      (node (ref "C1") (pin "2") (pinfunction "2_2") (pintype "passive"))
      (node (ref "C2") (pin "2") (pinfunction "2_2") (pintype "passive"))
      (node (ref "C3") (pin "2") (pinfunction "2_2") (pintype "passive"))
      (node (ref "C4") (pin "2") (pinfunction "2_2") (pintype "passive"))
      (node (ref "IC1") (pin "2") (pinfunction "GND_2") (pintype "power_in"))
      (node (ref "J1") (pin "1") (pinfunction "1_1") (pintype "passive"))
      (node (ref "J2") (pin "1") (pinfunction "1_1") (pintype "passive"))
      (node (ref "J3") (pin "13") (pinfunction "13_13") (pintype "passive"))
      (node (ref "J3") (pin "20") (pinfunction "20_20") (pintype "passive"))
      (node (ref "J3") (pin "5") (pinfunction "5_5") (pintype "passive"))
      (node (ref "J4") (pin "10") (pinfunction "10_10") (pintype "passive"))
      (node (ref "J4") (pin "15") (pinfunction "15_15") (pintype "passive"))
      (node (ref "J4") (pin "17") (pinfunction "17_17") (pintype "passive"))
      (node (ref "J4") (pin "3") (pinfunction "3_3") (pintype "passive"))
      (node (ref "J4") (pin "7") (pinfunction "7_7") (pintype "passive"))
      (node (ref "LED1") (pin "GND") (pinfunction "GND_GND") (pintype "power_in"))
      (node (ref "LED10") (pin "GND") (pinfunction "GND_GND") (pintype "power_in"))
      (node (ref "LED100") (pin "GND") (pinfunction "GND_GND") (pintype "power_in"))
      (node (ref "LED101") (pin "GND") (pinfunction "GND_GND") (pintype "power_in"))
      (node (ref "LED102") (pin "GND") (pinfunction "GND_GND") (pintype "power_in"))
      (node (ref "LED103") (pin "GND") (pinfunction "GND_GND") (pintype "power_in"))
      (node (ref "LED104") (pin "GND") (pinfunction "GND_GND") (pintype "power_in"))
      (node (ref "LED105") (pin "GND") (pinfunction "GND_GND") (pintype "power_in"))
      (node (ref "LED106") (pin "GND") (pinfunction "GND_GND") (pintype "power_in"))
      (node (ref "LED107") (pin "GND") (pinfunction "GND_GND") (pintype "power_in"))
      (node (ref "LED108") (pin "GND") (pinfunction "GND_GND") (pintype "power_in"))
      (node (ref "LED109") (pin "GND") (pinfunction "GND_GND") (pintype "power_in"))
      (node (ref "LED11") (pin "GND") (pinfunction "GND_GND") (pintype "power_in"))
      (node (ref "LED110") (pin "GND") (pinfunction "GND_GND") (pintype "power_in"))
      (node (ref "LED111") (pin "GND") (pinfunction "GND_GND") (pintype "power_in"))
      (node (ref "LED112") (pin "GND") (pinfunction "GND_GND") (pintype "power_in"))
      (node (ref "LED113") (pin "GND") (pinfunction "GND_GND") (pintype "power_in"))
      (node (ref "LED114") (pin "GND") (pinfunction "GND_GND") (pintype "power_in"))
      (node (ref "LED115") (pin "GND") (pinfunction "GND_GND") (pintype "power_in"))
      (node (ref "LED116") (pin "GND") (pinfunction "GND_GND") (pintype "power_in"))
      (node (ref "LED117") (pin "GND") (pinfunction "GND_GND") (pintype "power_in"))
      (node (ref "LED118") (pin "GND") (pinfunction "GND_GND") (pintype "power_in"))
      (node (ref "LED119") (pin "GND") (pinfunction "GND_GND") (pintype "power_in"))
      (node (ref "LED12") (pin "GND") (pinfunction "GND_GND") (pintype "power_in"))
      (node (ref "LED120") (pin "GND") (pinfunction "GND_GND") (pintype "power_in"))
      (node (ref "LED121") (pin "GND") (pinfunction "GND_GND") (pintype "power_in"))
      (node (ref "LED122") (pin "GND") (pinfunction "GND_GND") (pintype "power_in"))
      (node (ref "LED123") (pin "GND") (pinfunction "GND_GND") (pintype "power_in"))
      (node (ref "LED124") (pin "GND") (pinfunction "GND_GND") (pintype "power_in"))
      (node (ref "LED125") (pin "GND") (pinfunction "GND_GND") (pintype "power_in"))
      (node (ref "LED126") (pin "GND") (pinfunction "GND_GND") (pintype "power_in"))
      (node (ref "LED127") (pin "GND") (pinfunction "GND_GND") (pintype "power_in"))
      (node (ref "LED128") (pin "GND") (pinfunction "GND_GND") (pintype "power_in"))
      (node (ref "LED129") (pin "GND") (pinfunction "GND_GND") (pintype "power_in"))
      (node (ref "LED13") (pin "GND") (pinfunction "GND_GND") (pintype "power_in"))
      (node (ref "LED130") (pin "GND") (pinfunction "GND_GND") (pintype "power_in"))
      (node (ref "LED131") (pin "GND") (pinfunction "GND_GND") (pintype "power_in"))
      (node (ref "LED132") (pin "GND") (pinfunction "GND_GND") (pintype "power_in"))
      (node (ref "LED133") (pin "GND") (pinfunction "GND_GND") (pintype "power_in"))
      (node (ref "LED134") (pin "GND") (pinfunction "GND_GND") (pintype "power_in"))
      (node (ref "LED135") (pin "GND") (pinfunction "GND_GND") (pintype "power_in"))
      (node (ref "LED136") (pin "GND") (pinfunction "GND_GND") (pintype "power_in"))
      (node (ref "LED137") (pin "GND") (pinfunction "GND_GND") (pintype "power_in"))
      (node (ref "LED138") (pin "GND") (pinfunction "GND_GND") (pintype "power_in"))
      (node (ref "LED139") (pin "GND") (pinfunction "GND_GND") (pintype "power_in"))
      (node (ref "LED14") (pin "GND") (pinfunction "GND_GND") (pintype "power_in"))
      (node (ref "LED140") (pin "GND") (pinfunction "GND_GND") (pintype "power_in"))
      (node (ref "LED141") (pin "GND") (pinfunction "GND_GND") (pintype "power_in"))
      (node (ref "LED142") (pin "GND") (pinfunction "GND_GND") (pintype "power_in"))
      (node (ref "LED143") (pin "GND") (pinfunction "GND_GND") (pintype "power_in"))
      (node (ref "LED144") (pin "GND") (pinfunction "GND_GND") (pintype "power_in"))
      (node (ref "LED15") (pin "GND") (pinfunction "GND_GND") (pintype "power_in"))
      (node (ref "LED16") (pin "GND") (pinfunction "GND_GND") (pintype "power_in"))
      (node (ref "LED17") (pin "GND") (pinfunction "GND_GND") (pintype "power_in"))
      (node (ref "LED18") (pin "GND") (pinfunction "GND_GND") (pintype "power_in"))
      (node (ref "LED19") (pin "GND") (pinfunction "GND_GND") (pintype "power_in"))
      (node (ref "LED2") (pin "GND") (pinfunction "GND_GND") (pintype "power_in"))
      (node (ref "LED20") (pin "GND") (pinfunction "GND_GND") (pintype "power_in"))
      (node (ref "LED21") (pin "GND") (pinfunction "GND_GND") (pintype "power_in"))
      (node (ref "LED22") (pin "GND") (pinfunction "GND_GND") (pintype "power_in"))
      (node (ref "LED23") (pin "GND") (pinfunction "GND_GND") (pintype "power_in"))
      (node (ref "LED24") (pin "GND") (pinfunction "GND_GND") (pintype "power_in"))
      (node (ref "LED25") (pin "GND") (pinfunction "GND_GND") (pintype "power_in"))
      (node (ref "LED26") (pin "GND") (pinfunction "GND_GND") (pintype "power_in"))
      (node (ref "LED27") (pin "GND") (pinfunction "GND_GND") (pintype "power_in"))
      (node (ref "LED28") (pin "GND") (pinfunction "GND_GND") (pintype "power_in"))
      (node (ref "LED29") (pin "GND") (pinfunction "GND_GND") (pintype "power_in"))
      (node (ref "LED3") (pin "GND") (pinfunction "GND_GND") (pintype "power_in"))
      (node (ref "LED30") (pin "GND") (pinfunction "GND_GND") (pintype "power_in"))
      (node (ref "LED31") (pin "GND") (pinfunction "GND_GND") (pintype "power_in"))
      (node (ref "LED32") (pin "GND") (pinfunction "GND_GND") (pintype "power_in"))
      (node (ref "LED33") (pin "GND") (pinfunction "GND_GND") (pintype "power_in"))
      (node (ref "LED34") (pin "GND") (pinfunction "GND_GND") (pintype "power_in"))
      (node (ref "LED35") (pin "GND") (pinfunction "GND_GND") (pintype "power_in"))
      (node (ref "LED36") (pin "GND") (pinfunction "GND_GND") (pintype "power_in"))
      (node (ref "LED37") (pin "GND") (pinfunction "GND_GND") (pintype "power_in"))
      (node (ref "LED38") (pin "GND") (pinfunction "GND_GND") (pintype "power_in"))
      (node (ref "LED39") (pin "GND") (pinfunction "GND_GND") (pintype "power_in"))
      (node (ref "LED4") (pin "GND") (pinfunction "GND_GND") (pintype "power_in"))
      (node (ref "LED40") (pin "GND") (pinfunction "GND_GND") (pintype "power_in"))
      (node (ref "LED41") (pin "GND") (pinfunction "GND_GND") (pintype "power_in"))
      (node (ref "LED42") (pin "GND") (pinfunction "GND_GND") (pintype "power_in"))
      (node (ref "LED43") (pin "GND") (pinfunction "GND_GND") (pintype "power_in"))
      (node (ref "LED44") (pin "GND") (pinfunction "GND_GND") (pintype "power_in"))
      (node (ref "LED45") (pin "GND") (pinfunction "GND_GND") (pintype "power_in"))
      (node (ref "LED46") (pin "GND") (pinfunction "GND_GND") (pintype "power_in"))
      (node (ref "LED47") (pin "GND") (pinfunction "GND_GND") (pintype "power_in"))
      (node (ref "LED48") (pin "GND") (pinfunction "GND_GND") (pintype "power_in"))
      (node (ref "LED49") (pin "GND") (pinfunction "GND_GND") (pintype "power_in"))
      (node (ref "LED5") (pin "GND") (pinfunction "GND_GND") (pintype "power_in"))
      (node (ref "LED50") (pin "GND") (pinfunction "GND_GND") (pintype "power_in"))
      (node (ref "LED51") (pin "GND") (pinfunction "GND_GND") (pintype "power_in"))
      (node (ref "LED52") (pin "GND") (pinfunction "GND_GND") (pintype "power_in"))
      (node (ref "LED53") (pin "GND") (pinfunction "GND_GND") (pintype "power_in"))
      (node (ref "LED54") (pin "GND") (pinfunction "GND_GND") (pintype "power_in"))
      (node (ref "LED55") (pin "GND") (pinfunction "GND_GND") (pintype "power_in"))
      (node (ref "LED56") (pin "GND") (pinfunction "GND_GND") (pintype "power_in"))
      (node (ref "LED57") (pin "GND") (pinfunction "GND_GND") (pintype "power_in"))
      (node (ref "LED58") (pin "GND") (pinfunction "GND_GND") (pintype "power_in"))
      (node (ref "LED59") (pin "GND") (pinfunction "GND_GND") (pintype "power_in"))
      (node (ref "LED6") (pin "GND") (pinfunction "GND_GND") (pintype "power_in"))
      (node (ref "LED60") (pin "GND") (pinfunction "GND_GND") (pintype "power_in"))
      (node (ref "LED61") (pin "GND") (pinfunction "GND_GND") (pintype "power_in"))
      (node (ref "LED62") (pin "GND") (pinfunction "GND_GND") (pintype "power_in"))
      (node (ref "LED63") (pin "GND") (pinfunction "GND_GND") (pintype "power_in"))
      (node (ref "LED64") (pin "GND") (pinfunction "GND_GND") (pintype "power_in"))
      (node (ref "LED65") (pin "GND") (pinfunction "GND_GND") (pintype "power_in"))
      (node (ref "LED66") (pin "GND") (pinfunction "GND_GND") (pintype "power_in"))
      (node (ref "LED67") (pin "GND") (pinfunction "GND_GND") (pintype "power_in"))
      (node (ref "LED68") (pin "GND") (pinfunction "GND_GND") (pintype "power_in"))
      (node (ref "LED69") (pin "GND") (pinfunction "GND_GND") (pintype "power_in"))
      (node (ref "LED7") (pin "GND") (pinfunction "GND_GND") (pintype "power_in"))
      (node (ref "LED70") (pin "GND") (pinfunction "GND_GND") (pintype "power_in"))
      (node (ref "LED71") (pin "GND") (pinfunction "GND_GND") (pintype "power_in"))
      (node (ref "LED72") (pin "GND") (pinfunction "GND_GND") (pintype "power_in"))
      (node (ref "LED73") (pin "GND") (pinfunction "GND_GND") (pintype "power_in"))
      (node (ref "LED74") (pin "GND") (pinfunction "GND_GND") (pintype "power_in"))
      (node (ref "LED75") (pin "GND") (pinfunction "GND_GND") (pintype "power_in"))
      (node (ref "LED76") (pin "GND") (pinfunction "GND_GND") (pintype "power_in"))
      (node (ref "LED77") (pin "GND") (pinfunction "GND_GND") (pintype "power_in"))
      (node (ref "LED78") (pin "GND") (pinfunction "GND_GND") (pintype "power_in"))
      (node (ref "LED79") (pin "GND") (pinfunction "GND_GND") (pintype "power_in"))
      (node (ref "LED8") (pin "GND") (pinfunction "GND_GND") (pintype "power_in"))
      (node (ref "LED80") (pin "GND") (pinfunction "GND_GND") (pintype "power_in"))
      (node (ref "LED81") (pin "GND") (pinfunction "GND_GND") (pintype "power_in"))
      (node (ref "LED82") (pin "GND") (pinfunction "GND_GND") (pintype "power_in"))
      (node (ref "LED83") (pin "GND") (pinfunction "GND_GND") (pintype "power_in"))
      (node (ref "LED84") (pin "GND") (pinfunction "GND_GND") (pintype "power_in"))
      (node (ref "LED85") (pin "GND") (pinfunction "GND_GND") (pintype "power_in"))
      (node (ref "LED86") (pin "GND") (pinfunction "GND_GND") (pintype "power_in"))
      (node (ref "LED87") (pin "GND") (pinfunction "GND_GND") (pintype "power_in"))
      (node (ref "LED88") (pin "GND") (pinfunction "GND_GND") (pintype "power_in"))
      (node (ref "LED89") (pin "GND") (pinfunction "GND_GND") (pintype "power_in"))
      (node (ref "LED9") (pin "GND") (pinfunction "GND_GND") (pintype "power_in"))
      (node (ref "LED90") (pin "GND") (pinfunction "GND_GND") (pintype "power_in"))
      (node (ref "LED91") (pin "GND") (pinfunction "GND_GND") (pintype "power_in"))
      (node (ref "LED92") (pin "GND") (pinfunction "GND_GND") (pintype "power_in"))
      (node (ref "LED93") (pin "GND") (pinfunction "GND_GND") (pintype "power_in"))
      (node (ref "LED94") (pin "GND") (pinfunction "GND_GND") (pintype "power_in"))
      (node (ref "LED95") (pin "GND") (pinfunction "GND_GND") (pintype "power_in"))
      (node (ref "LED96") (pin "GND") (pinfunction "GND_GND") (pintype "power_in"))
      (node (ref "LED97") (pin "GND") (pinfunction "GND_GND") (pintype "power_in"))
      (node (ref "LED98") (pin "GND") (pinfunction "GND_GND") (pintype "power_in"))
      (node (ref "LED99") (pin "GND") (pinfunction "GND_GND") (pintype "power_in"))
    )
    (net (code "8") (name "GPIO0") (class "Default")
      (node (ref "J3") (pin "14") (pinfunction "14_14") (pintype "passive"))
    )
    (net (code "9") (name "GPIO1") (class "Default")
      (node (ref "J4") (pin "14") (pinfunction "14_14") (pintype "passive"))
    )
    (net (code "10") (name "GPIO2") (class "Default")
      (node (ref "J3") (pin "2") (pinfunction "2_2") (pintype "passive"))
    )
    (net (code "11") (name "GPIO3") (class "Default")
      (node (ref "J3") (pin "3") (pinfunction "3_3") (pintype "passive"))
    )
    (net (code "12") (name "GPIO4") (class "Default")
      (node (ref "J3") (pin "4") (pinfunction "4_4") (pintype "passive"))
    )
    (net (code "13") (name "GPIO5") (class "Default")
      (node (ref "J3") (pin "15") (pinfunction "15_15") (pintype "passive"))
    )
    (net (code "14") (name "GPIO6") (class "Default")
      (node (ref "J3") (pin "16") (pinfunction "16_16") (pintype "passive"))
    )
    (net (code "15") (name "GPIO7") (class "Default")
      (node (ref "J4") (pin "13") (pinfunction "13_13") (pintype "passive"))
    )
    (net (code "16") (name "GPIO8") (class "Default")
      (node (ref "J4") (pin "12") (pinfunction "12_12") (pintype "passive"))
    )
    (net (code "17") (name "GPIO9") (class "Default")
      (node (ref "J3") (pin "11") (pinfunction "11_11") (pintype "passive"))
    )
    (net (code "18") (name "GPIO10") (class "Default")
      (node (ref "J3") (pin "10") (pinfunction "10_10") (pintype "passive"))
      (node (ref "SJ1") (pin "3") (pinfunction "3_3") (pintype "passive"))
    )
    (net (code "19") (name "GPIO11") (class "Default")
      (node (ref "J3") (pin "12") (pinfunction "12_12") (pintype "passive"))
    )
    (net (code "20") (name "GPIO12") (class "Default")
      (node (ref "J4") (pin "16") (pinfunction "16_16") (pintype "passive"))
    )
    (net (code "21") (name "GPIO13") (class "Default")
      (node (ref "J3") (pin "17") (pinfunction "17_17") (pintype "passive"))
    )
    (net (code "22") (name "GPIO14") (class "Default")
      (node (ref "J4") (pin "4") (pinfunction "4_4") (pintype "passive"))
    )
    (net (code "23") (name "GPIO15") (class "Default")
      (node (ref "J4") (pin "5") (pinfunction "5_5") (pintype "passive"))
    )
    (net (code "24") (name "GPIO16") (class "Default")
      (node (ref "J4") (pin "18") (pinfunction "18_18") (pintype "passive"))
    )
    (net (code "25") (name "GPIO17") (class "Default")
      (node (ref "J3") (pin "6") (pinfunction "6_6") (pintype "passive"))
    )
    (net (code "26") (name "GPIO18") (class "Default")
      (node (ref "J4") (pin "6") (pinfunction "6_6") (pintype "passive"))
      (node (ref "SJ1") (pin "4") (pinfunction "4_4") (pintype "passive"))
    )
    (net (code "27") (name "GPIO19") (class "Default")
      (node (ref "J3") (pin "18") (pinfunction "18_18") (pintype "passive"))
    )
    (net (code "28") (name "GPIO20") (class "Default")
      (node (ref "J4") (pin "19") (pinfunction "19_19") (pintype "passive"))
    )
    (net (code "29") (name "GPIO21") (class "Default")
      (node (ref "J4") (pin "20") (pinfunction "20_20") (pintype "passive"))
      (node (ref "SJ1") (pin "1") (pinfunction "1_1") (pintype "passive"))
    )
    (net (code "30") (name "GPIO22") (class "Default")
      (node (ref "J3") (pin "8") (pinfunction "8_8") (pintype "passive"))
    )
    (net (code "31") (name "GPIO23") (class "Default")
      (node (ref "J4") (pin "8") (pinfunction "8_8") (pintype "passive"))
    )
    (net (code "32") (name "GPIO24") (class "Default")
      (node (ref "J4") (pin "9") (pinfunction "9_9") (pintype "passive"))
    )
    (net (code "33") (name "GPIO25") (class "Default")
      (node (ref "J4") (pin "11") (pinfunction "11_11") (pintype "passive"))
    )
    (net (code "34") (name "GPIO26") (class "Default")
      (node (ref "J3") (pin "19") (pinfunction "19_19") (pintype "passive"))
    )
    (net (code "35") (name "GPIO27") (class "Default")
      (node (ref "J3") (pin "7") (pinfunction "7_7") (pintype "passive"))
    )
    (net (code "36") (name "Net-(IC1-OE)") (class "Default")
      (node (ref "IC1") (pin "5") (pinfunction "OE_5") (pintype "input"))
      (node (ref "R1") (pin "2") (pinfunction "2_2") (pintype "passive"))
    )
    (net (code "37") (name "Net-(LED1-PadDO)") (class "Default")
      (node (ref "LED1") (pin "DO") (pinfunction "DO_DO") (pintype "output"))
      (node (ref "LED2") (pin "DI") (pinfunction "DI_DI") (pintype "input"))
    )
    (net (code "38") (name "Net-(LED2-PadDO)") (class "Default")
      (node (ref "LED2") (pin "DO") (pinfunction "DO_DO") (pintype "output"))
      (node (ref "LED3") (pin "DI") (pinfunction "DI_DI") (pintype "input"))
    )
    (net (code "39") (name "Net-(LED3-PadDO)") (class "Default")
      (node (ref "LED3") (pin "DO") (pinfunction "DO_DO") (pintype "output"))
      (node (ref "LED4") (pin "DI") (pinfunction "DI_DI") (pintype "input"))
    )
    (net (code "40") (name "Net-(LED4-PadDO)") (class "Default")
      (node (ref "LED4") (pin "DO") (pinfunction "DO_DO") (pintype "output"))
      (node (ref "LED5") (pin "DI") (pinfunction "DI_DI") (pintype "input"))
    )
    (net (code "41") (name "Net-(LED5-PadDO)") (class "Default")
      (node (ref "LED5") (pin "DO") (pinfunction "DO_DO") (pintype "output"))
      (node (ref "LED6") (pin "DI") (pinfunction "DI_DI") (pintype "input"))
    )
    (net (code "42") (name "Net-(LED6-PadDO)") (class "Default")
      (node (ref "LED6") (pin "DO") (pinfunction "DO_DO") (pintype "output"))
      (node (ref "LED7") (pin "DI") (pinfunction "DI_DI") (pintype "input"))
    )
    (net (code "43") (name "Net-(LED7-PadDO)") (class "Default")
      (node (ref "LED7") (pin "DO") (pinfunction "DO_DO") (pintype "output"))
      (node (ref "LED8") (pin "DI") (pinfunction "DI_DI") (pintype "input"))
    )
    (net (code "44") (name "Net-(LED8-PadDO)") (class "Default")
      (node (ref "LED8") (pin "DO") (pinfunction "DO_DO") (pintype "output"))
      (node (ref "LED9") (pin "DI") (pinfunction "DI_DI") (pintype "input"))
    )
    (net (code "45") (name "Net-(LED10-PadDI)") (class "Default")
      (node (ref "LED10") (pin "DI") (pinfunction "DI_DI") (pintype "input"))
      (node (ref "LED9") (pin "DO") (pinfunction "DO_DO") (pintype "output"))
    )
    (net (code "46") (name "Net-(LED10-PadDO)") (class "Default")
      (node (ref "LED10") (pin "DO") (pinfunction "DO_DO") (pintype "output"))
      (node (ref "LED11") (pin "DI") (pinfunction "DI_DI") (pintype "input"))
    )
    (net (code "47") (name "Net-(LED11-PadDO)") (class "Default")
      (node (ref "LED11") (pin "DO") (pinfunction "DO_DO") (pintype "output"))
      (node (ref "LED12") (pin "DI") (pinfunction "DI_DI") (pintype "input"))
    )
    (net (code "48") (name "Net-(LED12-PadDO)") (class "Default")
      (node (ref "LED12") (pin "DO") (pinfunction "DO_DO") (pintype "output"))
      (node (ref "LED13") (pin "DI") (pinfunction "DI_DI") (pintype "input"))
    )
    (net (code "49") (name "Net-(LED13-PadDO)") (class "Default")
      (node (ref "LED13") (pin "DO") (pinfunction "DO_DO") (pintype "output"))
      (node (ref "LED14") (pin "DI") (pinfunction "DI_DI") (pintype "input"))
    )
    (net (code "50") (name "Net-(LED14-PadDO)") (class "Default")
      (node (ref "LED14") (pin "DO") (pinfunction "DO_DO") (pintype "output"))
      (node (ref "LED15") (pin "DI") (pinfunction "DI_DI") (pintype "input"))
    )
    (net (code "51") (name "Net-(LED15-PadDO)") (class "Default")
      (node (ref "LED15") (pin "DO") (pinfunction "DO_DO") (pintype "output"))
      (node (ref "LED16") (pin "DI") (pinfunction "DI_DI") (pintype "input"))
    )
    (net (code "52") (name "Net-(LED16-PadDO)") (class "Default")
      (node (ref "LED16") (pin "DO") (pinfunction "DO_DO") (pintype "output"))
      (node (ref "LED17") (pin "DI") (pinfunction "DI_DI") (pintype "input"))
    )
    (net (code "53") (name "Net-(LED17-PadDO)") (class "Default")
      (node (ref "LED17") (pin "DO") (pinfunction "DO_DO") (pintype "output"))
      (node (ref "LED18") (pin "DI") (pinfunction "DI_DI") (pintype "input"))
    )
    (net (code "54") (name "Net-(LED18-PadDO)") (class "Default")
      (node (ref "LED18") (pin "DO") (pinfunction "DO_DO") (pintype "output"))
      (node (ref "LED19") (pin "DI") (pinfunction "DI_DI") (pintype "input"))
    )
    (net (code "55") (name "Net-(LED19-PadDO)") (class "Default")
      (node (ref "LED19") (pin "DO") (pinfunction "DO_DO") (pintype "output"))
      (node (ref "LED20") (pin "DI") (pinfunction "DI_DI") (pintype "input"))
    )
    (net (code "56") (name "Net-(LED20-PadDO)") (class "Default")
      (node (ref "LED20") (pin "DO") (pinfunction "DO_DO") (pintype "output"))
      (node (ref "LED21") (pin "DI") (pinfunction "DI_DI") (pintype "input"))
    )
    (net (code "57") (name "Net-(LED21-PadDO)") (class "Default")
      (node (ref "LED21") (pin "DO") (pinfunction "DO_DO") (pintype "output"))
      (node (ref "LED22") (pin "DI") (pinfunction "DI_DI") (pintype "input"))
    )
    (net (code "58") (name "Net-(LED22-PadDO)") (class "Default")
      (node (ref "LED22") (pin "DO") (pinfunction "DO_DO") (pintype "output"))
      (node (ref "LED23") (pin "DI") (pinfunction "DI_DI") (pintype "input"))
    )
    (net (code "59") (name "Net-(LED23-PadDO)") (class "Default")
      (node (ref "LED23") (pin "DO") (pinfunction "DO_DO") (pintype "output"))
      (node (ref "LED24") (pin "DI") (pinfunction "DI_DI") (pintype "input"))
    )
    (net (code "60") (name "Net-(LED24-PadDO)") (class "Default")
      (node (ref "LED24") (pin "DO") (pinfunction "DO_DO") (pintype "output"))
      (node (ref "LED25") (pin "DI") (pinfunction "DI_DI") (pintype "input"))
    )
    (net (code "61") (name "Net-(LED25-PadDO)") (class "Default")
      (node (ref "LED25") (pin "DO") (pinfunction "DO_DO") (pintype "output"))
      (node (ref "LED26") (pin "DI") (pinfunction "DI_DI") (pintype "input"))
    )
    (net (code "62") (name "Net-(LED26-PadDO)") (class "Default")
      (node (ref "LED26") (pin "DO") (pinfunction "DO_DO") (pintype "output"))
      (node (ref "LED27") (pin "DI") (pinfunction "DI_DI") (pintype "input"))
    )
    (net (code "63") (name "Net-(LED27-PadDO)") (class "Default")
      (node (ref "LED27") (pin "DO") (pinfunction "DO_DO") (pintype "output"))
      (node (ref "LED28") (pin "DI") (pinfunction "DI_DI") (pintype "input"))
    )
    (net (code "64") (name "Net-(LED28-PadDO)") (class "Default")
      (node (ref "LED28") (pin "DO") (pinfunction "DO_DO") (pintype "output"))
      (node (ref "LED29") (pin "DI") (pinfunction "DI_DI") (pintype "input"))
    )
    (net (code "65") (name "Net-(LED29-PadDO)") (class "Default")
      (node (ref "LED29") (pin "DO") (pinfunction "DO_DO") (pintype "output"))
      (node (ref "LED30") (pin "DI") (pinfunction "DI_DI") (pintype "input"))
    )
    (net (code "66") (name "Net-(LED30-PadDO)") (class "Default")
      (node (ref "LED30") (pin "DO") (pinfunction "DO_DO") (pintype "output"))
      (node (ref "LED31") (pin "DI") (pinfunction "DI_DI") (pintype "input"))
    )
    (net (code "67") (name "Net-(LED31-PadDO)") (class "Default")
      (node (ref "LED31") (pin "DO") (pinfunction "DO_DO") (pintype "output"))
      (node (ref "LED32") (pin "DI") (pinfunction "DI_DI") (pintype "input"))
    )
    (net (code "68") (name "Net-(LED32-PadDO)") (class "Default")
      (node (ref "LED32") (pin "DO") (pinfunction "DO_DO") (pintype "output"))
      (node (ref "LED33") (pin "DI") (pinfunction "DI_DI") (pintype "input"))
    )
    (net (code "69") (name "Net-(LED33-PadDO)") (class "Default")
      (node (ref "LED33") (pin "DO") (pinfunction "DO_DO") (pintype "output"))
      (node (ref "LED34") (pin "DI") (pinfunction "DI_DI") (pintype "input"))
    )
    (net (code "70") (name "Net-(LED34-PadDO)") (class "Default")
      (node (ref "LED34") (pin "DO") (pinfunction "DO_DO") (pintype "output"))
      (node (ref "LED35") (pin "DI") (pinfunction "DI_DI") (pintype "input"))
    )
    (net (code "71") (name "Net-(LED35-PadDO)") (class "Default")
      (node (ref "LED35") (pin "DO") (pinfunction "DO_DO") (pintype "output"))
      (node (ref "LED36") (pin "DI") (pinfunction "DI_DI") (pintype "input"))
    )
    (net (code "72") (name "Net-(LED36-PadDO)") (class "Default")
      (node (ref "LED36") (pin "DO") (pinfunction "DO_DO") (pintype "output"))
      (node (ref "LED37") (pin "DI") (pinfunction "DI_DI") (pintype "input"))
    )
    (net (code "73") (name "Net-(LED37-PadDO)") (class "Default")
      (node (ref "LED37") (pin "DO") (pinfunction "DO_DO") (pintype "output"))
      (node (ref "LED38") (pin "DI") (pinfunction "DI_DI") (pintype "input"))
    )
    (net (code "74") (name "Net-(LED38-PadDO)") (class "Default")
      (node (ref "LED38") (pin "DO") (pinfunction "DO_DO") (pintype "output"))
      (node (ref "LED39") (pin "DI") (pinfunction "DI_DI") (pintype "input"))
    )
    (net (code "75") (name "Net-(LED39-PadDO)") (class "Default")
      (node (ref "LED39") (pin "DO") (pinfunction "DO_DO") (pintype "output"))
      (node (ref "LED40") (pin "DI") (pinfunction "DI_DI") (pintype "input"))
    )
    (net (code "76") (name "Net-(LED40-PadDO)") (class "Default")
      (node (ref "LED40") (pin "DO") (pinfunction "DO_DO") (pintype "output"))
      (node (ref "LED41") (pin "DI") (pinfunction "DI_DI") (pintype "input"))
    )
    (net (code "77") (name "Net-(LED41-PadDO)") (class "Default")
      (node (ref "LED41") (pin "DO") (pinfunction "DO_DO") (pintype "output"))
      (node (ref "LED42") (pin "DI") (pinfunction "DI_DI") (pintype "input"))
    )
    (net (code "78") (name "Net-(LED42-PadDO)") (class "Default")
      (node (ref "LED42") (pin "DO") (pinfunction "DO_DO") (pintype "output"))
      (node (ref "LED43") (pin "DI") (pinfunction "DI_DI") (pintype "input"))
    )
    (net (code "79") (name "Net-(LED43-PadDO)") (class "Default")
      (node (ref "LED43") (pin "DO") (pinfunction "DO_DO") (pintype "output"))
      (node (ref "LED44") (pin "DI") (pinfunction "DI_DI") (pintype "input"))
    )
    (net (code "80") (name "Net-(LED44-PadDO)") (class "Default")
      (node (ref "LED44") (pin "DO") (pinfunction "DO_DO") (pintype "output"))
      (node (ref "LED45") (pin "DI") (pinfunction "DI_DI") (pintype "input"))
    )
    (net (code "81") (name "Net-(LED45-PadDO)") (class "Default")
      (node (ref "LED45") (pin "DO") (pinfunction "DO_DO") (pintype "output"))
      (node (ref "LED46") (pin "DI") (pinfunction "DI_DI") (pintype "input"))
    )
    (net (code "82") (name "Net-(LED46-PadDO)") (class "Default")
      (node (ref "LED46") (pin "DO") (pinfunction "DO_DO") (pintype "output"))
      (node (ref "LED47") (pin "DI") (pinfunction "DI_DI") (pintype "input"))
    )
    (net (code "83") (name "Net-(LED47-PadDO)") (class "Default")
      (node (ref "LED47") (pin "DO") (pinfunction "DO_DO") (pintype "output"))
      (node (ref "LED48") (pin "DI") (pinfunction "DI_DI") (pintype "input"))
    )
    (net (code "84") (name "Net-(LED48-PadDO)") (class "Default")
      (node (ref "LED48") (pin "DO") (pinfunction "DO_DO") (pintype "output"))
      (node (ref "LED49") (pin "DI") (pinfunction "DI_DI") (pintype "input"))
    )
    (net (code "85") (name "Net-(LED49-PadDO)") (class "Default")
      (node (ref "LED49") (pin "DO") (pinfunction "DO_DO") (pintype "output"))
      (node (ref "LED50") (pin "DI") (pinfunction "DI_DI") (pintype "input"))
    )
    (net (code "86") (name "Net-(LED50-PadDO)") (class "Default")
      (node (ref "LED50") (pin "DO") (pinfunction "DO_DO") (pintype "output"))
      (node (ref "LED51") (pin "DI") (pinfunction "DI_DI") (pintype "input"))
    )
    (net (code "87") (name "Net-(LED51-PadDO)") (class "Default")
      (node (ref "LED51") (pin "DO") (pinfunction "DO_DO") (pintype "output"))
      (node (ref "LED52") (pin "DI") (pinfunction "DI_DI") (pintype "input"))
    )
    (net (code "88") (name "Net-(LED52-PadDO)") (class "Default")
      (node (ref "LED52") (pin "DO") (pinfunction "DO_DO") (pintype "output"))
      (node (ref "LED53") (pin "DI") (pinfunction "DI_DI") (pintype "input"))
    )
    (net (code "89") (name "Net-(LED53-PadDO)") (class "Default")
      (node (ref "LED53") (pin "DO") (pinfunction "DO_DO") (pintype "output"))
      (node (ref "LED54") (pin "DI") (pinfunction "DI_DI") (pintype "input"))
    )
    (net (code "90") (name "Net-(LED54-PadDO)") (class "Default")
      (node (ref "LED54") (pin "DO") (pinfunction "DO_DO") (pintype "output"))
      (node (ref "LED55") (pin "DI") (pinfunction "DI_DI") (pintype "input"))
    )
    (net (code "91") (name "Net-(LED55-PadDO)") (class "Default")
      (node (ref "LED55") (pin "DO") (pinfunction "DO_DO") (pintype "output"))
      (node (ref "LED56") (pin "DI") (pinfunction "DI_DI") (pintype "input"))
    )
    (net (code "92") (name "Net-(LED56-PadDO)") (class "Default")
      (node (ref "LED56") (pin "DO") (pinfunction "DO_DO") (pintype "output"))
      (node (ref "LED57") (pin "DI") (pinfunction "DI_DI") (pintype "input"))
    )
    (net (code "93") (name "Net-(LED57-PadDO)") (class "Default")
      (node (ref "LED57") (pin "DO") (pinfunction "DO_DO") (pintype "output"))
      (node (ref "LED58") (pin "DI") (pinfunction "DI_DI") (pintype "input"))
    )
    (net (code "94") (name "Net-(LED58-PadDO)") (class "Default")
      (node (ref "LED58") (pin "DO") (pinfunction "DO_DO") (pintype "output"))
      (node (ref "LED59") (pin "DI") (pinfunction "DI_DI") (pintype "input"))
    )
    (net (code "95") (name "Net-(LED59-PadDO)") (class "Default")
      (node (ref "LED59") (pin "DO") (pinfunction "DO_DO") (pintype "output"))
      (node (ref "LED60") (pin "DI") (pinfunction "DI_DI") (pintype "input"))
    )
    (net (code "96") (name "Net-(LED60-PadDO)") (class "Default")
      (node (ref "LED60") (pin "DO") (pinfunction "DO_DO") (pintype "output"))
      (node (ref "LED61") (pin "DI") (pinfunction "DI_DI") (pintype "input"))
    )
    (net (code "97") (name "Net-(LED61-PadDO)") (class "Default")
      (node (ref "LED61") (pin "DO") (pinfunction "DO_DO") (pintype "output"))
      (node (ref "LED62") (pin "DI") (pinfunction "DI_DI") (pintype "input"))
    )
    (net (code "98") (name "Net-(LED62-PadDO)") (class "Default")
      (node (ref "LED62") (pin "DO") (pinfunction "DO_DO") (pintype "output"))
      (node (ref "LED63") (pin "DI") (pinfunction "DI_DI") (pintype "input"))
    )
    (net (code "99") (name "Net-(LED63-PadDO)") (class "Default")
      (node (ref "LED63") (pin "DO") (pinfunction "DO_DO") (pintype "output"))
      (node (ref "LED64") (pin "DI") (pinfunction "DI_DI") (pintype "input"))
    )
    (net (code "100") (name "Net-(LED64-PadDO)") (class "Default")
      (node (ref "LED64") (pin "DO") (pinfunction "DO_DO") (pintype "output"))
      (node (ref "LED65") (pin "DI") (pinfunction "DI_DI") (pintype "input"))
    )
    (net (code "101") (name "Net-(LED65-PadDO)") (class "Default")
      (node (ref "LED65") (pin "DO") (pinfunction "DO_DO") (pintype "output"))
      (node (ref "LED66") (pin "DI") (pinfunction "DI_DI") (pintype "input"))
    )
    (net (code "102") (name "Net-(LED66-PadDO)") (class "Default")
      (node (ref "LED66") (pin "DO") (pinfunction "DO_DO") (pintype "output"))
      (node (ref "LED67") (pin "DI") (pinfunction "DI_DI") (pintype "input"))
    )
    (net (code "103") (name "Net-(LED67-PadDO)") (class "Default")
      (node (ref "LED67") (pin "DO") (pinfunction "DO_DO") (pintype "output"))
      (node (ref "LED68") (pin "DI") (pinfunction "DI_DI") (pintype "input"))
    )
    (net (code "104") (name "Net-(LED68-PadDO)") (class "Default")
      (node (ref "LED68") (pin "DO") (pinfunction "DO_DO") (pintype "output"))
      (node (ref "LED69") (pin "DI") (pinfunction "DI_DI") (pintype "input"))
    )
    (net (code "105") (name "Net-(LED69-PadDO)") (class "Default")
      (node (ref "LED69") (pin "DO") (pinfunction "DO_DO") (pintype "output"))
      (node (ref "LED70") (pin "DI") (pinfunction "DI_DI") (pintype "input"))
    )
    (net (code "106") (name "Net-(LED70-PadDO)") (class "Default")
      (node (ref "LED70") (pin "DO") (pinfunction "DO_DO") (pintype "output"))
      (node (ref "LED71") (pin "DI") (pinfunction "DI_DI") (pintype "input"))
    )
    (net (code "107") (name "Net-(LED71-PadDO)") (class "Default")
      (node (ref "LED71") (pin "DO") (pinfunction "DO_DO") (pintype "output"))
      (node (ref "LED72") (pin "DI") (pinfunction "DI_DI") (pintype "input"))
    )
    (net (code "108") (name "Net-(LED73-PadDO)") (class "Default")
      (node (ref "LED73") (pin "DO") (pinfunction "DO_DO") (pintype "output"))
      (node (ref "LED74") (pin "DI") (pinfunction "DI_DI") (pintype "input"))
    )
    (net (code "109") (name "Net-(LED74-PadDO)") (class "Default")
      (node (ref "LED74") (pin "DO") (pinfunction "DO_DO") (pintype "output"))
      (node (ref "LED75") (pin "DI") (pinfunction "DI_DI") (pintype "input"))
    )
    (net (code "110") (name "Net-(LED75-PadDO)") (class "Default")
      (node (ref "LED75") (pin "DO") (pinfunction "DO_DO") (pintype "output"))
      (node (ref "LED76") (pin "DI") (pinfunction "DI_DI") (pintype "input"))
    )
    (net (code "111") (name "Net-(LED76-PadDO)") (class "Default")
      (node (ref "LED76") (pin "DO") (pinfunction "DO_DO") (pintype "output"))
      (node (ref "LED77") (pin "DI") (pinfunction "DI_DI") (pintype "input"))
    )
    (net (code "112") (name "Net-(LED77-PadDO)") (class "Default")
      (node (ref "LED77") (pin "DO") (pinfunction "DO_DO") (pintype "output"))
      (node (ref "LED78") (pin "DI") (pinfunction "DI_DI") (pintype "input"))
    )
    (net (code "113") (name "Net-(LED78-PadDO)") (class "Default")
      (node (ref "LED78") (pin "DO") (pinfunction "DO_DO") (pintype "output"))
      (node (ref "LED79") (pin "DI") (pinfunction "DI_DI") (pintype "input"))
    )
    (net (code "114") (name "Net-(LED79-PadDO)") (class "Default")
      (node (ref "LED79") (pin "DO") (pinfunction "DO_DO") (pintype "output"))
      (node (ref "LED80") (pin "DI") (pinfunction "DI_DI") (pintype "input"))
    )
    (net (code "115") (name "Net-(LED80-PadDO)") (class "Default")
      (node (ref "LED80") (pin "DO") (pinfunction "DO_DO") (pintype "output"))
      (node (ref "LED81") (pin "DI") (pinfunction "DI_DI") (pintype "input"))
    )
    (net (code "116") (name "Net-(LED81-PadDO)") (class "Default")
      (node (ref "LED81") (pin "DO") (pinfunction "DO_DO") (pintype "output"))
      (node (ref "LED82") (pin "DI") (pinfunction "DI_DI") (pintype "input"))
    )
    (net (code "117") (name "Net-(LED82-PadDO)") (class "Default")
      (node (ref "LED82") (pin "DO") (pinfunction "DO_DO") (pintype "output"))
      (node (ref "LED83") (pin "DI") (pinfunction "DI_DI") (pintype "input"))
    )
    (net (code "118") (name "Net-(LED83-PadDO)") (class "Default")
      (node (ref "LED83") (pin "DO") (pinfunction "DO_DO") (pintype "output"))
      (node (ref "LED84") (pin "DI") (pinfunction "DI_DI") (pintype "input"))
    )
    (net (code "119") (name "Net-(LED84-PadDO)") (class "Default")
      (node (ref "LED84") (pin "DO") (pinfunction "DO_DO") (pintype "output"))
      (node (ref "LED85") (pin "DI") (pinfunction "DI_DI") (pintype "input"))
    )
    (net (code "120") (name "Net-(LED85-PadDO)") (class "Default")
      (node (ref "LED85") (pin "DO") (pinfunction "DO_DO") (pintype "output"))
      (node (ref "LED86") (pin "DI") (pinfunction "DI_DI") (pintype "input"))
    )
    (net (code "121") (name "Net-(LED86-PadDO)") (class "Default")
      (node (ref "LED86") (pin "DO") (pinfunction "DO_DO") (pintype "output"))
      (node (ref "LED87") (pin "DI") (pinfunction "DI_DI") (pintype "input"))
    )
    (net (code "122") (name "Net-(LED87-PadDO)") (class "Default")
      (node (ref "LED87") (pin "DO") (pinfunction "DO_DO") (pintype "output"))
      (node (ref "LED88") (pin "DI") (pinfunction "DI_DI") (pintype "input"))
    )
    (net (code "123") (name "Net-(LED88-PadDO)") (class "Default")
      (node (ref "LED88") (pin "DO") (pinfunction "DO_DO") (pintype "output"))
      (node (ref "LED89") (pin "DI") (pinfunction "DI_DI") (pintype "input"))
    )
    (net (code "124") (name "Net-(LED89-PadDO)") (class "Default")
      (node (ref "LED89") (pin "DO") (pinfunction "DO_DO") (pintype "output"))
      (node (ref "LED90") (pin "DI") (pinfunction "DI_DI") (pintype "input"))
    )
    (net (code "125") (name "Net-(LED90-PadDO)") (class "Default")
      (node (ref "LED90") (pin "DO") (pinfunction "DO_DO") (pintype "output"))
      (node (ref "LED91") (pin "DI") (pinfunction "DI_DI") (pintype "input"))
    )
    (net (code "126") (name "Net-(LED91-PadDO)") (class "Default")
      (node (ref "LED91") (pin "DO") (pinfunction "DO_DO") (pintype "output"))
      (node (ref "LED92") (pin "DI") (pinfunction "DI_DI") (pintype "input"))
    )
    (net (code "127") (name "Net-(LED92-PadDO)") (class "Default")
      (node (ref "LED92") (pin "DO") (pinfunction "DO_DO") (pintype "output"))
      (node (ref "LED93") (pin "DI") (pinfunction "DI_DI") (pintype "input"))
    )
    (net (code "128") (name "Net-(LED93-PadDO)") (class "Default")
      (node (ref "LED93") (pin "DO") (pinfunction "DO_DO") (pintype "output"))
      (node (ref "LED94") (pin "DI") (pinfunction "DI_DI") (pintype "input"))
    )
    (net (code "129") (name "Net-(LED94-PadDO)") (class "Default")
      (node (ref "LED94") (pin "DO") (pinfunction "DO_DO") (pintype "output"))
      (node (ref "LED95") (pin "DI") (pinfunction "DI_DI") (pintype "input"))
    )
    (net (code "130") (name "Net-(LED95-PadDO)") (class "Default")
      (node (ref "LED95") (pin "DO") (pinfunction "DO_DO") (pintype "output"))
      (node (ref "LED96") (pin "DI") (pinfunction "DI_DI") (pintype "input"))
    )
    (net (code "131") (name "Net-(LED96-PadDO)") (class "Default")
      (node (ref "LED96") (pin "DO") (pinfunction "DO_DO") (pintype "output"))
      (node (ref "LED97") (pin "DI") (pinfunction "DI_DI") (pintype "input"))
    )
    (net (code "132") (name "Net-(LED97-PadDO)") (class "Default")
      (node (ref "LED97") (pin "DO") (pinfunction "DO_DO") (pintype "output"))
      (node (ref "LED98") (pin "DI") (pinfunction "DI_DI") (pintype "input"))
    )
    (net (code "133") (name "Net-(LED98-PadDO)") (class "Default")
      (node (ref "LED98") (pin "DO") (pinfunction "DO_DO") (pintype "output"))
      (node (ref "LED99") (pin "DI") (pinfunction "DI_DI") (pintype "input"))
    )
    (net (code "134") (name "Net-(LED100-PadDI)") (class "Default")
      (node (ref "LED100") (pin "DI") (pinfunction "DI_DI") (pintype "input"))
      (node (ref "LED99") (pin "DO") (pinfunction "DO_DO") (pintype "output"))
    )
    (net (code "135") (name "Net-(LED100-PadDO)") (class "Default")
      (node (ref "LED100") (pin "DO") (pinfunction "DO_DO") (pintype "output"))
      (node (ref "LED101") (pin "DI") (pinfunction "DI_DI") (pintype "input"))
    )
    (net (code "136") (name "Net-(LED101-PadDO)") (class "Default")
      (node (ref "LED101") (pin "DO") (pinfunction "DO_DO") (pintype "output"))
      (node (ref "LED102") (pin "DI") (pinfunction "DI_DI") (pintype "input"))
    )
    (net (code "137") (name "Net-(LED102-PadDO)") (class "Default")
      (node (ref "LED102") (pin "DO") (pinfunction "DO_DO") (pintype "output"))
      (node (ref "LED103") (pin "DI") (pinfunction "DI_DI") (pintype "input"))
    )
    (net (code "138") (name "Net-(LED103-PadDO)") (class "Default")
      (node (ref "LED103") (pin "DO") (pinfunction "DO_DO") (pintype "output"))
      (node (ref "LED104") (pin "DI") (pinfunction "DI_DI") (pintype "input"))
    )
    (net (code "139") (name "Net-(LED104-PadDO)") (class "Default")
      (node (ref "LED104") (pin "DO") (pinfunction "DO_DO") (pintype "output"))
      (node (ref "LED105") (pin "DI") (pinfunction "DI_DI") (pintype "input"))
    )
    (net (code "140") (name "Net-(LED105-PadDO)") (class "Default")
      (node (ref "LED105") (pin "DO") (pinfunction "DO_DO") (pintype "output"))
      (node (ref "LED106") (pin "DI") (pinfunction "DI_DI") (pintype "input"))
    )
    (net (code "141") (name "Net-(LED106-PadDO)") (class "Default")
      (node (ref "LED106") (pin "DO") (pinfunction "DO_DO") (pintype "output"))
      (node (ref "LED107") (pin "DI") (pinfunction "DI_DI") (pintype "input"))
    )
    (net (code "142") (name "Net-(LED107-PadDO)") (class "Default")
      (node (ref "LED107") (pin "DO") (pinfunction "DO_DO") (pintype "output"))
      (node (ref "LED108") (pin "DI") (pinfunction "DI_DI") (pintype "input"))
    )
    (net (code "143") (name "Net-(LED108-PadDO)") (class "Default")
      (node (ref "LED108") (pin "DO") (pinfunction "DO_DO") (pintype "output"))
      (node (ref "LED109") (pin "DI") (pinfunction "DI_DI") (pintype "input"))
    )
    (net (code "144") (name "Net-(LED109-PadDO)") (class "Default")
      (node (ref "LED109") (pin "DO") (pinfunction "DO_DO") (pintype "output"))
      (node (ref "LED110") (pin "DI") (pinfunction "DI_DI") (pintype "input"))
    )
    (net (code "145") (name "Net-(LED110-PadDO)") (class "Default")
      (node (ref "LED110") (pin "DO") (pinfunction "DO_DO") (pintype "output"))
      (node (ref "LED111") (pin "DI") (pinfunction "DI_DI") (pintype "input"))
    )
    (net (code "146") (name "Net-(LED111-PadDO)") (class "Default")
      (node (ref "LED111") (pin "DO") (pinfunction "DO_DO") (pintype "output"))
      (node (ref "LED112") (pin "DI") (pinfunction "DI_DI") (pintype "input"))
    )
    (net (code "147") (name "Net-(LED112-PadDO)") (class "Default")
      (node (ref "LED112") (pin "DO") (pinfunction "DO_DO") (pintype "output"))
      (node (ref "LED113") (pin "DI") (pinfunction "DI_DI") (pintype "input"))
    )
    (net (code "148") (name "Net-(LED113-PadDO)") (class "Default")
      (node (ref "LED113") (pin "DO") (pinfunction "DO_DO") (pintype "output"))
      (node (ref "LED114") (pin "DI") (pinfunction "DI_DI") (pintype "input"))
    )
    (net (code "149") (name "Net-(LED114-PadDO)") (class "Default")
      (node (ref "LED114") (pin "DO") (pinfunction "DO_DO") (pintype "output"))
      (node (ref "LED115") (pin "DI") (pinfunction "DI_DI") (pintype "input"))
    )
    (net (code "150") (name "Net-(LED115-PadDO)") (class "Default")
      (node (ref "LED115") (pin "DO") (pinfunction "DO_DO") (pintype "output"))
      (node (ref "LED116") (pin "DI") (pinfunction "DI_DI") (pintype "input"))
    )
    (net (code "151") (name "Net-(LED116-PadDO)") (class "Default")
      (node (ref "LED116") (pin "DO") (pinfunction "DO_DO") (pintype "output"))
      (node (ref "LED117") (pin "DI") (pinfunction "DI_DI") (pintype "input"))
    )
    (net (code "152") (name "Net-(LED117-PadDO)") (class "Default")
      (node (ref "LED117") (pin "DO") (pinfunction "DO_DO") (pintype "output"))
      (node (ref "LED118") (pin "DI") (pinfunction "DI_DI") (pintype "input"))
    )
    (net (code "153") (name "Net-(LED118-PadDO)") (class "Default")
      (node (ref "LED118") (pin "DO") (pinfunction "DO_DO") (pintype "output"))
      (node (ref "LED119") (pin "DI") (pinfunction "DI_DI") (pintype "input"))
    )
    (net (code "154") (name "Net-(LED119-PadDO)") (class "Default")
      (node (ref "LED119") (pin "DO") (pinfunction "DO_DO") (pintype "output"))
      (node (ref "LED120") (pin "DI") (pinfunction "DI_DI") (pintype "input"))
    )
    (net (code "155") (name "Net-(LED120-PadDO)") (class "Default")
      (node (ref "LED120") (pin "DO") (pinfunction "DO_DO") (pintype "output"))
      (node (ref "LED121") (pin "DI") (pinfunction "DI_DI") (pintype "input"))
    )
    (net (code "156") (name "Net-(LED121-PadDO)") (class "Default")
      (node (ref "LED121") (pin "DO") (pinfunction "DO_DO") (pintype "output"))
      (node (ref "LED122") (pin "DI") (pinfunction "DI_DI") (pintype "input"))
    )
    (net (code "157") (name "Net-(LED122-PadDO)") (class "Default")
      (node (ref "LED122") (pin "DO") (pinfunction "DO_DO") (pintype "output"))
      (node (ref "LED123") (pin "DI") (pinfunction "DI_DI") (pintype "input"))
    )
    (net (code "158") (name "Net-(LED123-PadDO)") (class "Default")
      (node (ref "LED123") (pin "DO") (pinfunction "DO_DO") (pintype "output"))
      (node (ref "LED124") (pin "DI") (pinfunction "DI_DI") (pintype "input"))
    )
    (net (code "159") (name "Net-(LED124-PadDO)") (class "Default")
      (node (ref "LED124") (pin "DO") (pinfunction "DO_DO") (pintype "output"))
      (node (ref "LED125") (pin "DI") (pinfunction "DI_DI") (pintype "input"))
    )
    (net (code "160") (name "Net-(LED125-PadDO)") (class "Default")
      (node (ref "LED125") (pin "DO") (pinfunction "DO_DO") (pintype "output"))
      (node (ref "LED126") (pin "DI") (pinfunction "DI_DI") (pintype "input"))
    )
    (net (code "161") (name "Net-(LED126-PadDO)") (class "Default")
      (node (ref "LED126") (pin "DO") (pinfunction "DO_DO") (pintype "output"))
      (node (ref "LED127") (pin "DI") (pinfunction "DI_DI") (pintype "input"))
    )
    (net (code "162") (name "Net-(LED127-PadDO)") (class "Default")
      (node (ref "LED127") (pin "DO") (pinfunction "DO_DO") (pintype "output"))
      (node (ref "LED128") (pin "DI") (pinfunction "DI_DI") (pintype "input"))
    )
    (net (code "163") (name "Net-(LED128-PadDO)") (class "Default")
      (node (ref "LED128") (pin "DO") (pinfunction "DO_DO") (pintype "output"))
      (node (ref "LED129") (pin "DI") (pinfunction "DI_DI") (pintype "input"))
    )
    (net (code "164") (name "Net-(LED129-PadDO)") (class "Default")
      (node (ref "LED129") (pin "DO") (pinfunction "DO_DO") (pintype "output"))
      (node (ref "LED130") (pin "DI") (pinfunction "DI_DI") (pintype "input"))
    )
    (net (code "165") (name "Net-(LED130-PadDO)") (class "Default")
      (node (ref "LED130") (pin "DO") (pinfunction "DO_DO") (pintype "output"))
      (node (ref "LED131") (pin "DI") (pinfunction "DI_DI") (pintype "input"))
    )
    (net (code "166") (name "Net-(LED131-PadDO)") (class "Default")
      (node (ref "LED131") (pin "DO") (pinfunction "DO_DO") (pintype "output"))
      (node (ref "LED132") (pin "DI") (pinfunction "DI_DI") (pintype "input"))
    )
    (net (code "167") (name "Net-(LED132-PadDO)") (class "Default")
      (node (ref "LED132") (pin "DO") (pinfunction "DO_DO") (pintype "output"))
      (node (ref "LED133") (pin "DI") (pinfunction "DI_DI") (pintype "input"))
    )
    (net (code "168") (name "Net-(LED133-PadDO)") (class "Default")
      (node (ref "LED133") (pin "DO") (pinfunction "DO_DO") (pintype "output"))
      (node (ref "LED134") (pin "DI") (pinfunction "DI_DI") (pintype "input"))
    )
    (net (code "169") (name "Net-(LED134-PadDO)") (class "Default")
      (node (ref "LED134") (pin "DO") (pinfunction "DO_DO") (pintype "output"))
      (node (ref "LED135") (pin "DI") (pinfunction "DI_DI") (pintype "input"))
    )
    (net (code "170") (name "Net-(LED135-PadDO)") (class "Default")
      (node (ref "LED135") (pin "DO") (pinfunction "DO_DO") (pintype "output"))
      (node (ref "LED136") (pin "DI") (pinfunction "DI_DI") (pintype "input"))
    )
    (net (code "171") (name "Net-(LED136-PadDO)") (class "Default")
      (node (ref "LED136") (pin "DO") (pinfunction "DO_DO") (pintype "output"))
      (node (ref "LED137") (pin "DI") (pinfunction "DI_DI") (pintype "input"))
    )
    (net (code "172") (name "Net-(LED137-PadDO)") (class "Default")
      (node (ref "LED137") (pin "DO") (pinfunction "DO_DO") (pintype "output"))
      (node (ref "LED138") (pin "DI") (pinfunction "DI_DI") (pintype "input"))
    )
    (net (code "173") (name "Net-(LED138-PadDO)") (class "Default")
      (node (ref "LED138") (pin "DO") (pinfunction "DO_DO") (pintype "output"))
      (node (ref "LED139") (pin "DI") (pinfunction "DI_DI") (pintype "input"))
    )
    (net (code "174") (name "Net-(LED139-PadDO)") (class "Default")
      (node (ref "LED139") (pin "DO") (pinfunction "DO_DO") (pintype "output"))
      (node (ref "LED140") (pin "DI") (pinfunction "DI_DI") (pintype "input"))
    )
    (net (code "175") (name "Net-(LED140-PadDO)") (class "Default")
      (node (ref "LED140") (pin "DO") (pinfunction "DO_DO") (pintype "output"))
      (node (ref "LED141") (pin "DI") (pinfunction "DI_DI") (pintype "input"))
    )
    (net (code "176") (name "Net-(LED141-PadDO)") (class "Default")
      (node (ref "LED141") (pin "DO") (pinfunction "DO_DO") (pintype "output"))
      (node (ref "LED142") (pin "DI") (pinfunction "DI_DI") (pintype "input"))
    )
    (net (code "177") (name "Net-(LED142-PadDO)") (class "Default")
      (node (ref "LED142") (pin "DO") (pinfunction "DO_DO") (pintype "output"))
      (node (ref "LED143") (pin "DI") (pinfunction "DI_DI") (pintype "input"))
    )
    (net (code "178") (name "Net-(LED143-PadDO)") (class "Default")
      (node (ref "LED143") (pin "DO") (pinfunction "DO_DO") (pintype "output"))
      (node (ref "LED144") (pin "DI") (pinfunction "DI_DI") (pintype "input"))
    )
  )
)
